# Telephone.net
KiCad netlist of a schematic drawn in Altium Designer
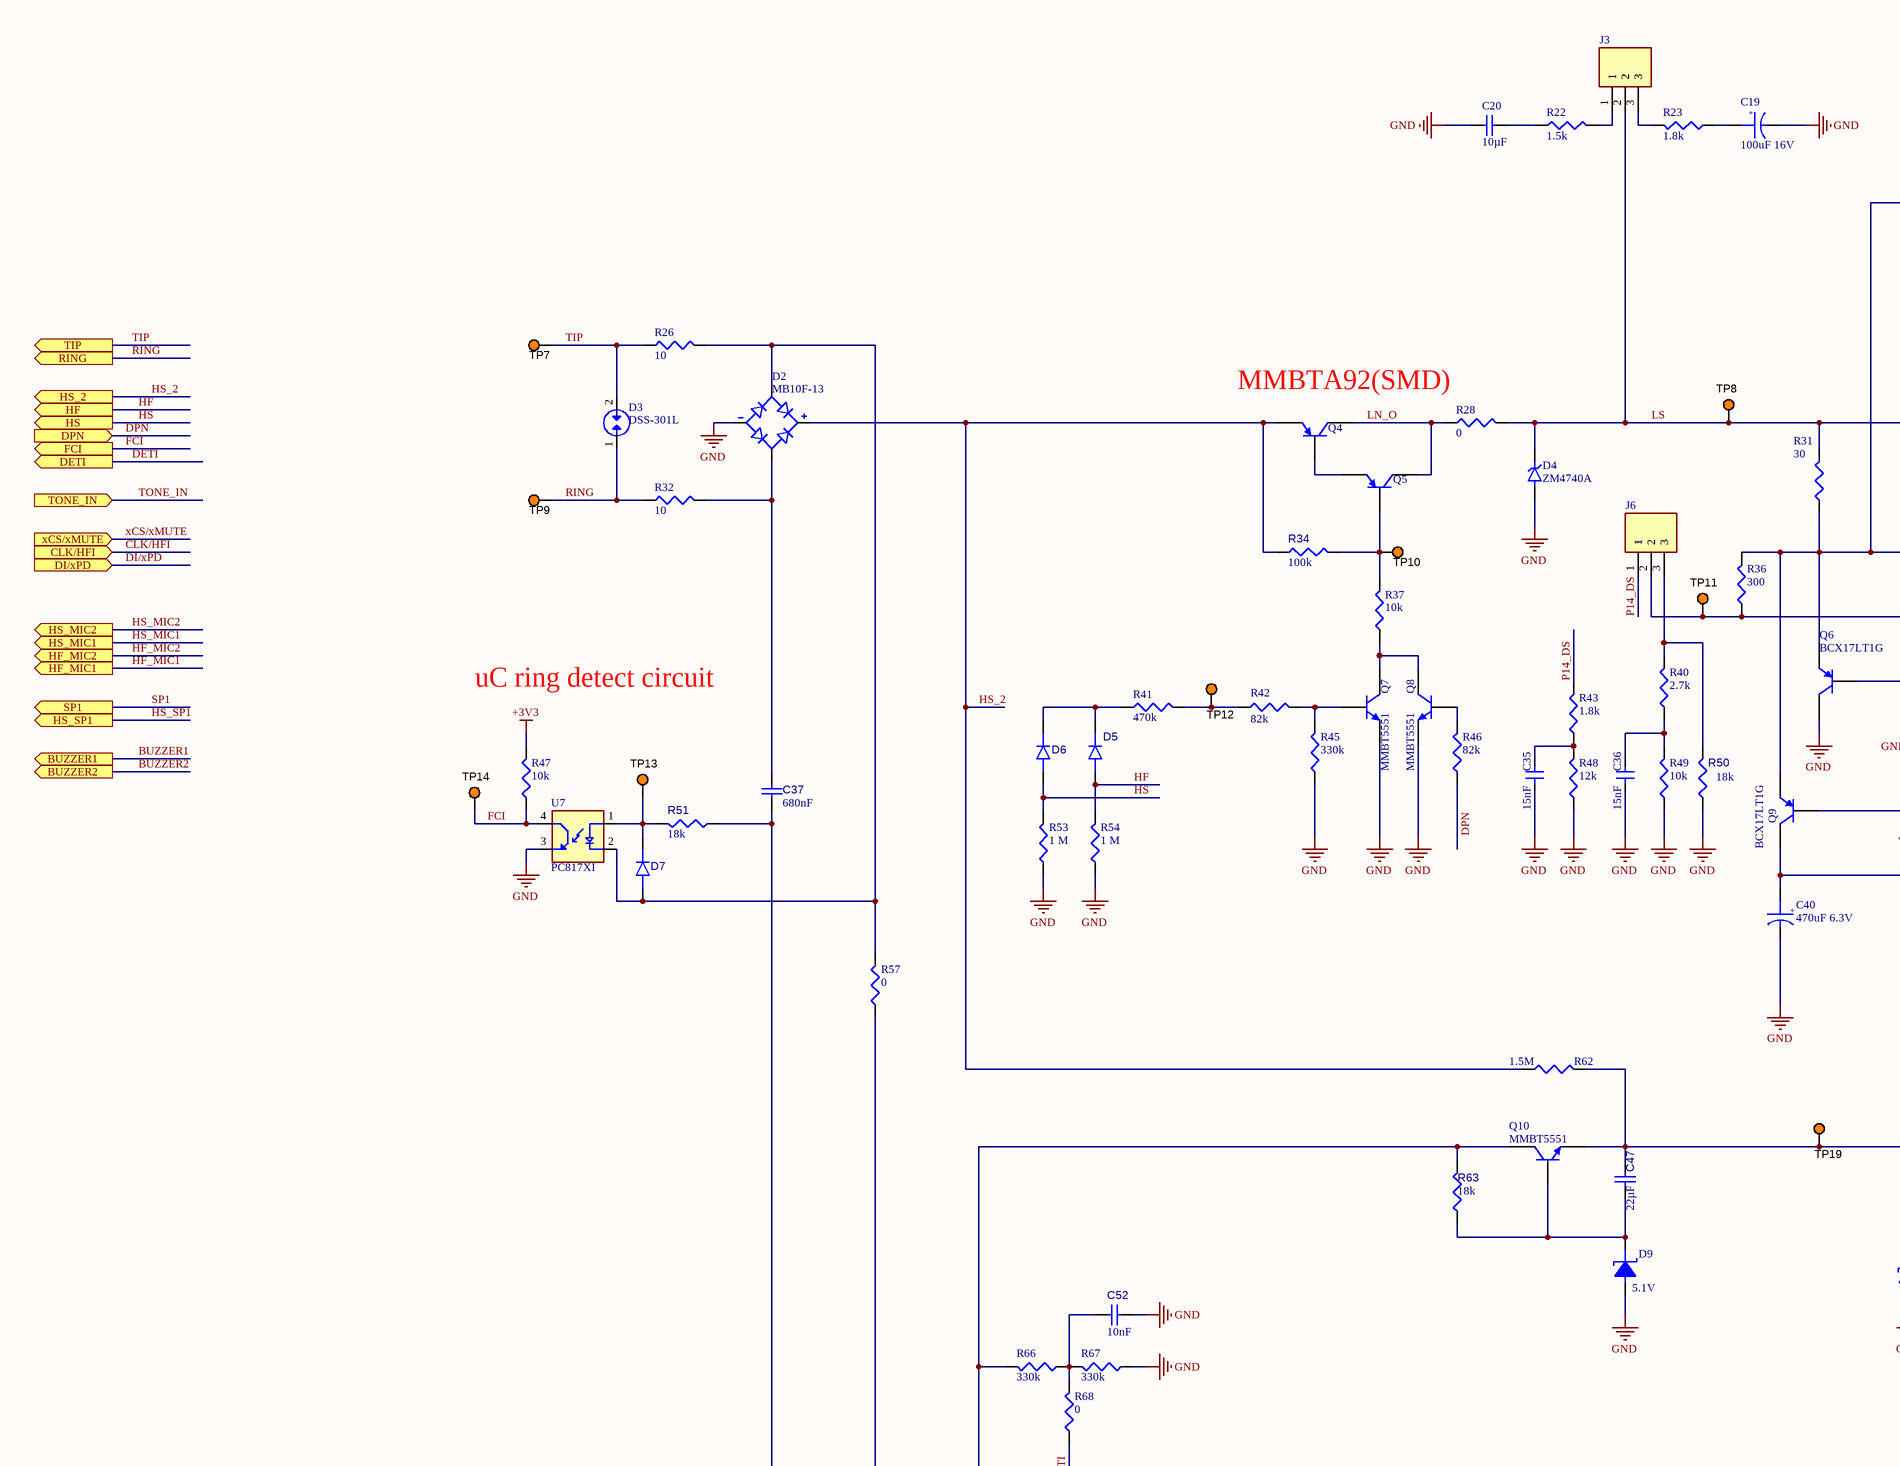
[diagram p0: Telephone.SchDoc, top left]
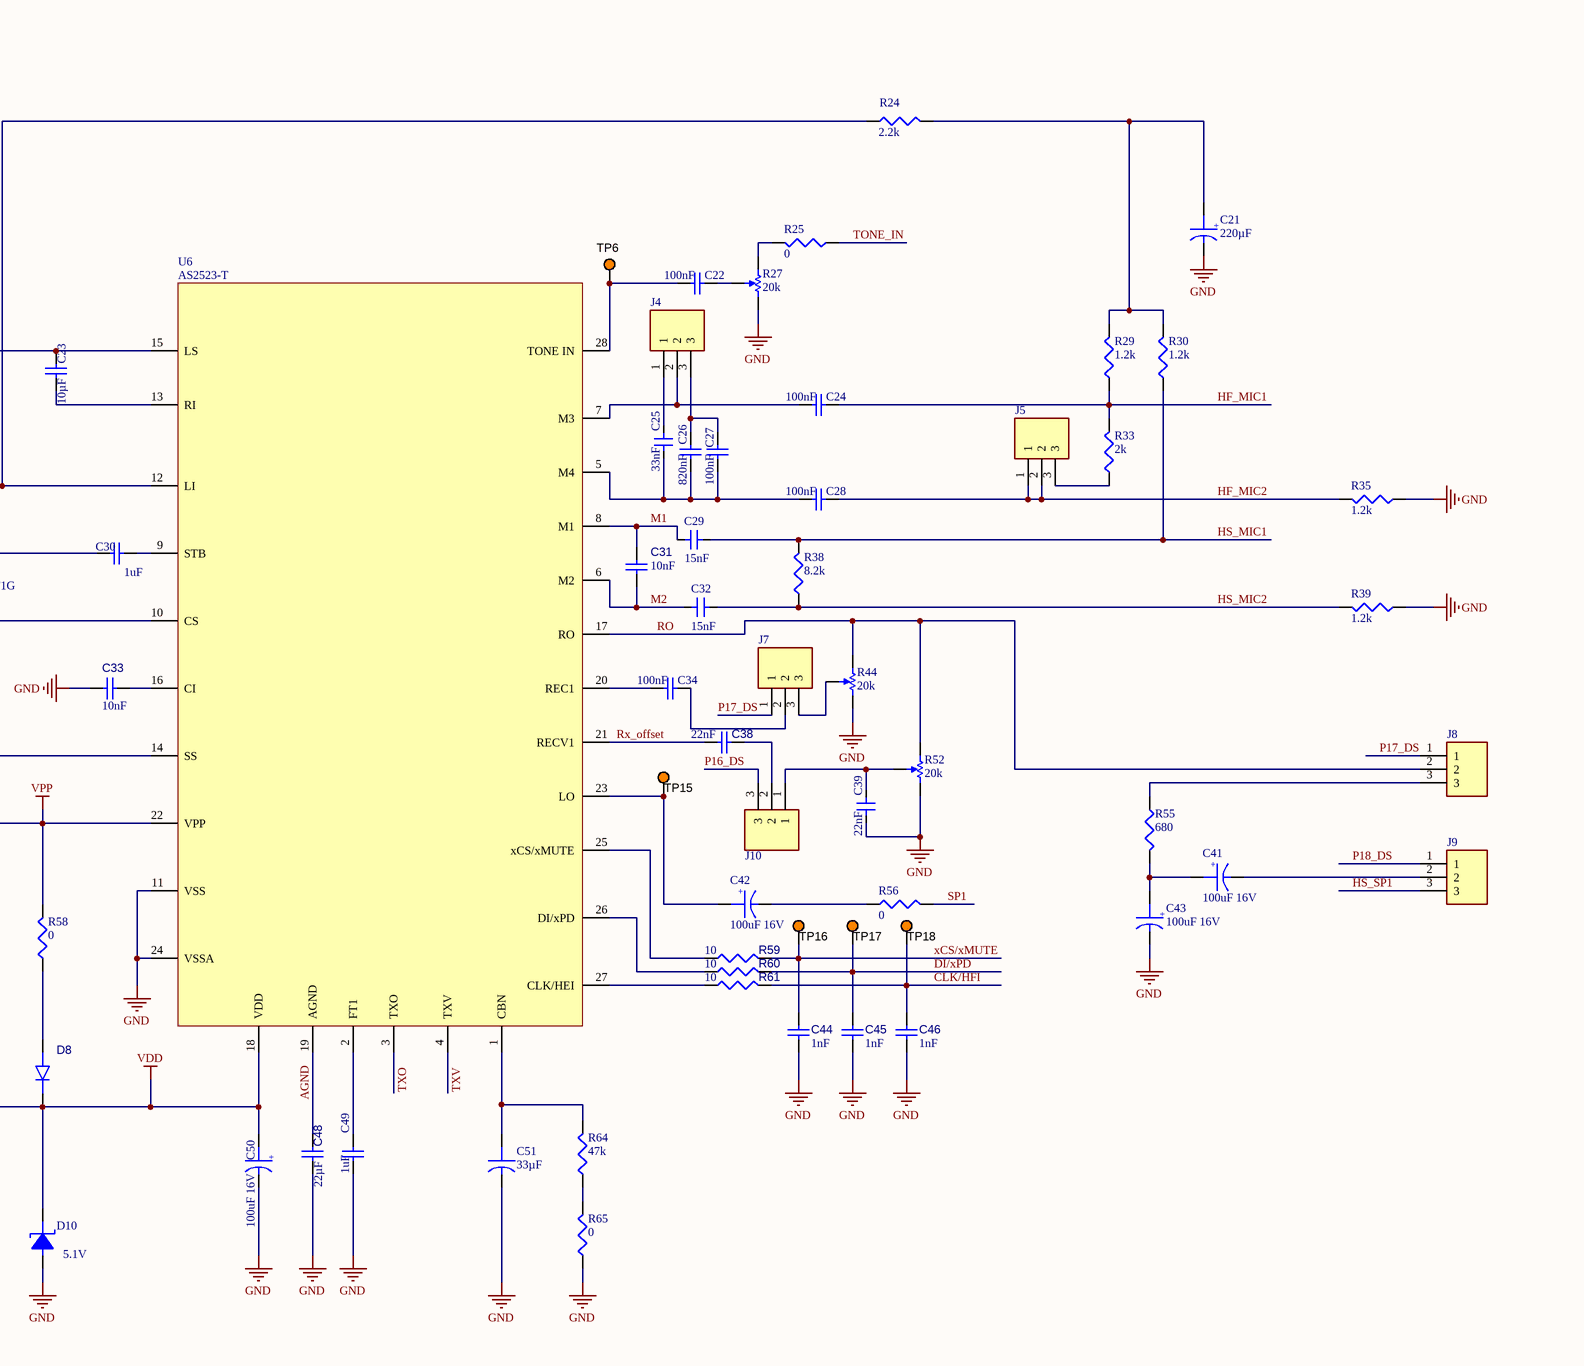
[diagram p1: Telephone.SchDoc, top right]
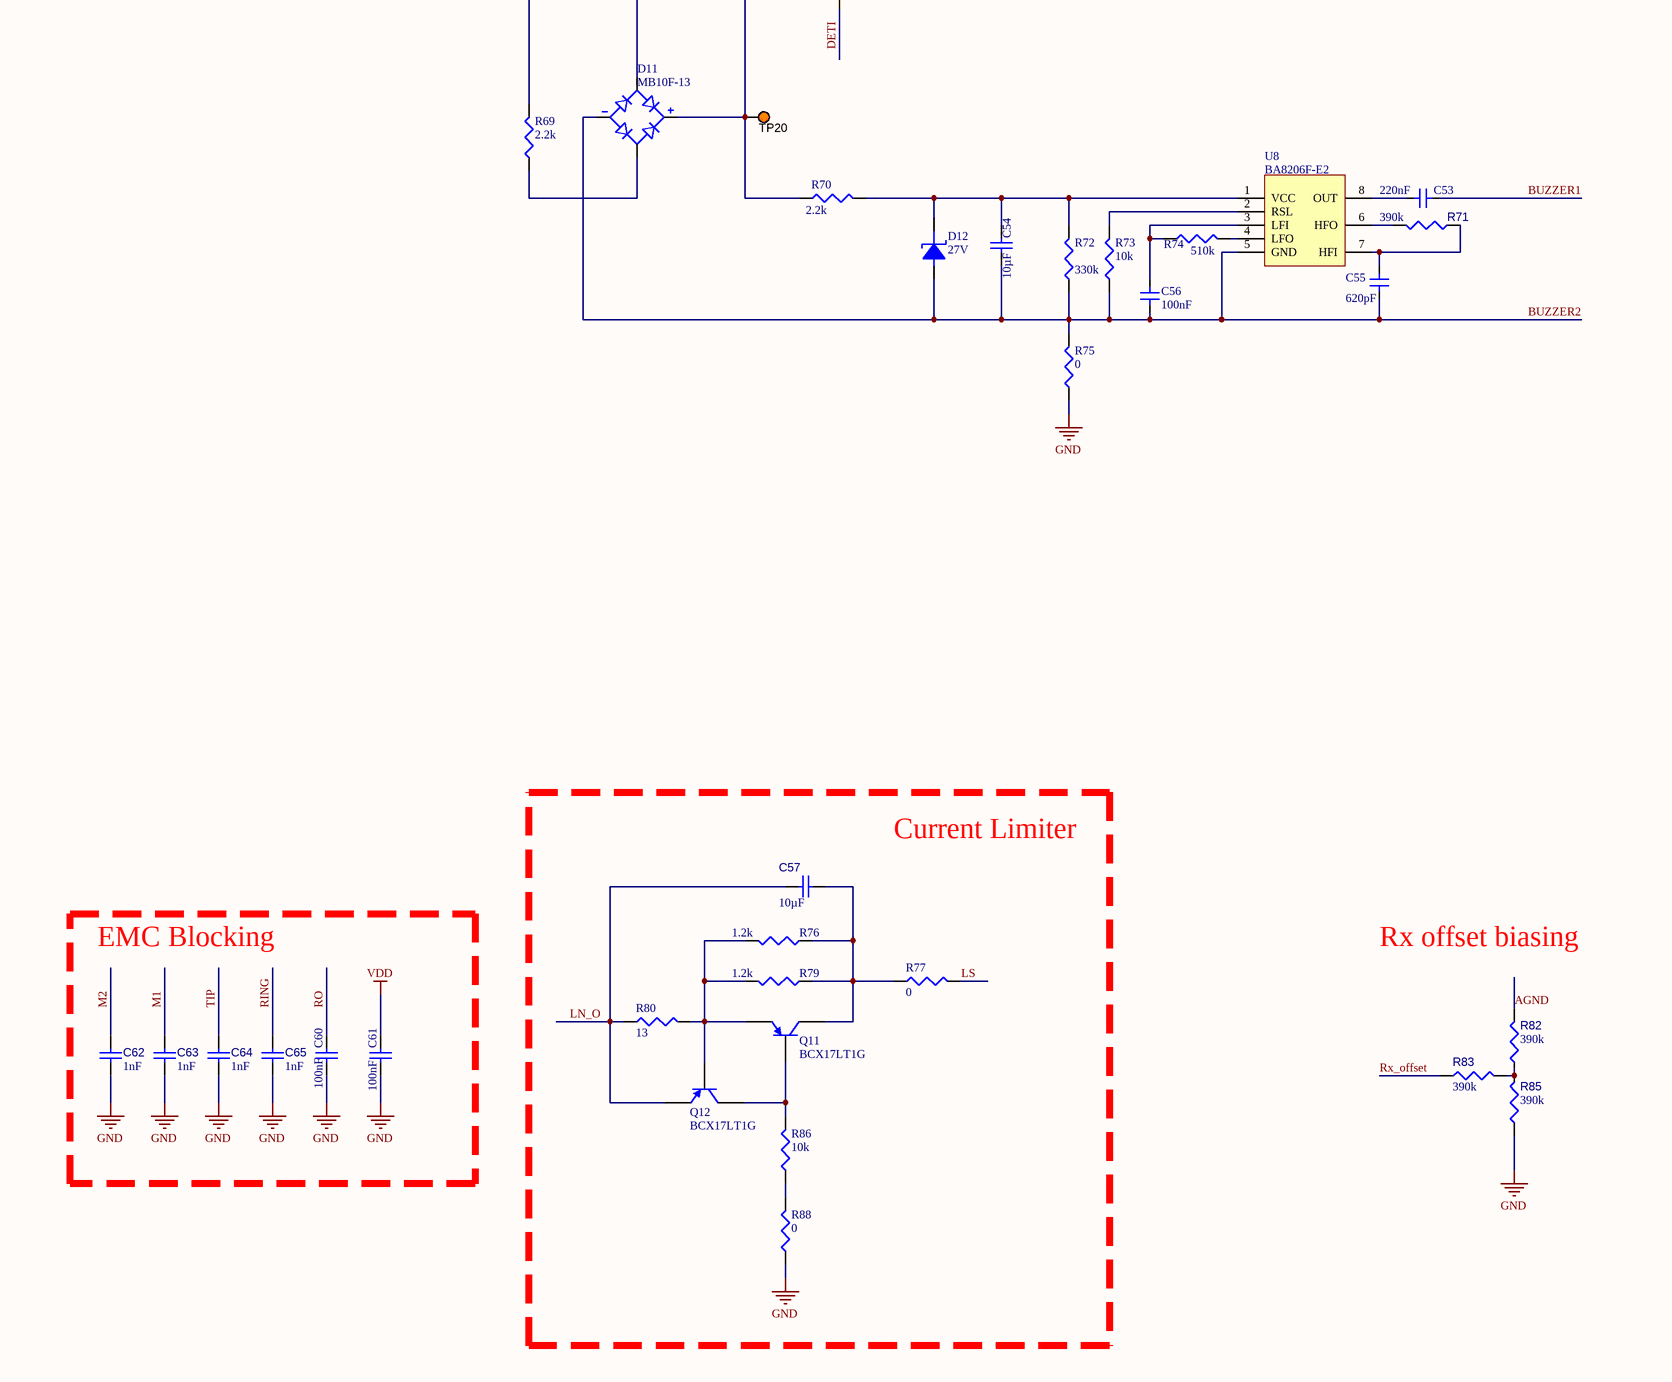
[diagram p2: Telephone.SchDoc, bottom left]
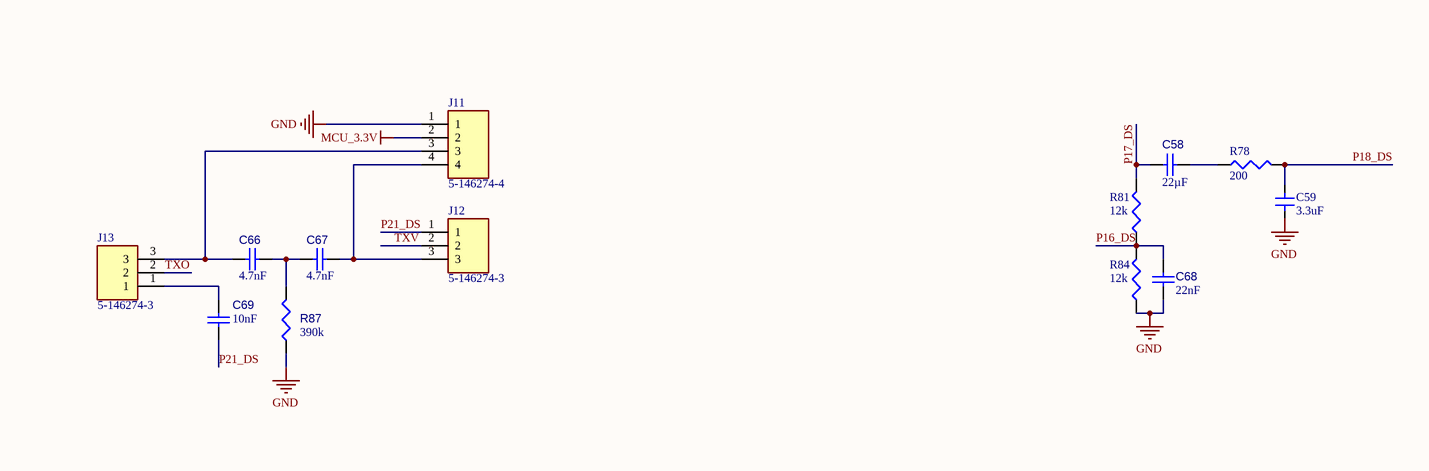
[diagram p3: Telephone.SchDoc, bottom right]

(export (version "E")
  (design (tool "Eeschema 10.0.6"))
  (components
    (comp (ref "C19")
      (value "100uF 16V")
      (footprint "CAPAE6767X56M 100UF 16V")
      (description "ALU Electrolytic; SMD; EEV; +105°C; 16VDC; 6.3µF; 6.3 x 5.4")
      (fields
        (field (name "MANUFACTURER") "KEMET")
        (field (name "MANUFACTURER PART NUMBER") "EEV107M016S9GAA")
      )
      (libsource (lib "Kish Spark") (part "EEV107M016S9GAA"))
    )
    (comp (ref "C20")
      (value "10µF")
      (footprint "C1210")
      (description "Capacitor 10 uF 35 VDC 1210, GRM32ER7YA106KA12L, Murata")
      (fields
        (field (name "TOLERANCE") "10%")
        (field (name "VOLTAGE") "35V")
        (field (name "SOURCE") "PTZLib.SchLib")
      )
      (libsource (lib "Kish Spark") (part "CAP-NP-2"))
    )
    (comp (ref "C21")
      (value "220µF")
      (footprint "CAPAE9290X56M 220UF 6.3V")
      (fields
        (field (name "MANUFACTURER") "Wurth Electronics")
        (field (name "MANUFACTURER PART NUMBER") "865080143009")
        (field (name "TOLERANCE") "20%")
      )
      (libsource (lib "Kish Spark") (part "EEV107M016S9GAA"))
    )
    (comp (ref "C22")
      (value "100nF")
      (footprint "C0603")
      (description "YAGEO - CC0603KRX7R8BB104 - CERAMIC CAPACITOR, 0.1UF, 25V, X7R, 10%, 0603, FULL REEL")
      (fields
        (field (name "TOLERANCE") "10%")
        (field (name "VOLTAGE") "25V")
        (field (name "SOURCE") "PTZLib.SchLib")
      )
      (libsource (lib "Kish Spark") (part "CAP-NP-2"))
    )
    (comp (ref "C23")
      (value "10µF")
      (footprint "C1210")
      (description "Capacitor 10 uF 35 VDC 1210, GRM32ER7YA106KA12L, Murata")
      (fields
        (field (name "TOLERANCE") "10%")
        (field (name "VOLTAGE") "35V")
        (field (name "SOURCE") "PTZLib.SchLib")
      )
      (libsource (lib "Kish Spark") (part "CAP-NP-2"))
    )
    (comp (ref "C24")
      (value "100nF")
      (footprint "C0603")
      (description "YAGEO - CC0603KRX7R8BB104 - CERAMIC CAPACITOR, 0.1UF, 25V, X7R, 10%, 0603, FULL REEL")
      (fields
        (field (name "TOLERANCE") "10%")
        (field (name "VOLTAGE") "25V")
        (field (name "SOURCE") "PTZLib.SchLib")
      )
      (libsource (lib "Kish Spark") (part "CAP-NP-2"))
    )
    (comp (ref "C25")
      (value "33nF")
      (footprint "0805")
      (description "Chip Capacitor 0805 MLCC X7R 0.033 uF+/ -20% 100 V T&R MH")
      (fields
        (field (name "MANUFACTURER") "Walsin Technologies")
        (field (name "MANUFACTURER PART NUMBER") "0805B333M101CT")
      )
      (libsource (lib "Kish Spark") (part "C0805C472K5RAC7210_1"))
    )
    (comp (ref "C26")
      (value "820nF")
      (footprint "C0603")
      (description "0603 820 nF 16 V ±10 % Tolerance X7R SMT Multilayer Ceramic Capacitor")
      (fields (field (name "TOLERANCE") "10%") (field (name "MANUFACTURER") "Yageo"))
      (libsource (lib "Kish Spark") (part "CAP-NP-2"))
    )
    (comp (ref "C27")
      (value "100nF")
      (footprint "C0603")
      (description "YAGEO - CC0603KRX7R8BB104 - CERAMIC CAPACITOR, 0.1UF, 25V, X7R, 10%, 0603, FULL REEL")
      (fields
        (field (name "TOLERANCE") "10%")
        (field (name "VOLTAGE") "25V")
        (field (name "SOURCE") "PTZLib.SchLib")
      )
      (libsource (lib "Kish Spark") (part "CAP-NP-2"))
    )
    (comp (ref "C28")
      (value "100nF")
      (footprint "C0603")
      (description "YAGEO - CC0603KRX7R8BB104 - CERAMIC CAPACITOR, 0.1UF, 25V, X7R, 10%, 0603, FULL REEL")
      (fields
        (field (name "TOLERANCE") "10%")
        (field (name "VOLTAGE") "25V")
        (field (name "SOURCE") "PTZLib.SchLib")
      )
      (libsource (lib "Kish Spark") (part "CAP-NP-2"))
    )
    (comp (ref "C29")
      (value "15nF")
      (footprint "0805")
      (description "Multilayer Ceramic Capacitor, 0.015 F, 10%, X7R, 50 V, 0805 [2012 Metric] RoHS Compliant: Yes")
      (fields
        (field (name "MANUFACTURER") "Walsin Technologies")
        (field (name "MANUFACTURER PART NUMBER") "0805B153K500CT")
      )
      (libsource (lib "Kish Spark") (part "C0805C472K5RAC7210_1"))
    )
    (comp (ref "C30")
      (value "1uF")
      (footprint "EVIDC:C0603")
      (description "Cap_1uF_10%_X5R_25V_0603")
      (fields (field (name "MANUFACTURER") "Samsung") (field (name "MFR PART NO") "CL10A105KA8NNNC"))
      (libsource (lib "EVIDC") (part "Cap_1uF_25V_0603"))
    )
    (comp (ref "C31")
      (value "10nF")
      (footprint "C0603")
      (description "0603 10nF 50 V ±10 % Tolerance X7R Surface Mount Multilayer Ceramic Capacitor")
      (fields (field (name "TOLERANCE") "10%") (field (name "MANUFACTURER") "Kyocera AVX"))
      (libsource (lib "Kish Spark") (part "CAP-NP-2"))
    )
    (comp (ref "C32")
      (value "15nF")
      (footprint "0805")
      (description "Multilayer Ceramic Capacitor, 0.015 F, 10%, X7R, 50 V, 0805 [2012 Metric] RoHS Compliant: Yes")
      (fields
        (field (name "MANUFACTURER") "Walsin Technologies")
        (field (name "MANUFACTURER PART NUMBER") "0805B153K500CT")
      )
      (libsource (lib "Kish Spark") (part "C0805C472K5RAC7210_1"))
    )
    (comp (ref "C33")
      (value "10nF")
      (footprint "C0603")
      (description "0603 10nF 50 V ±10 % Tolerance X7R Surface Mount Multilayer Ceramic Capacitor")
      (fields (field (name "TOLERANCE") "10%") (field (name "MANUFACTURER") "Kyocera AVX"))
      (libsource (lib "Kish Spark") (part "CAP-NP-2"))
    )
    (comp (ref "C34")
      (value "100nF")
      (footprint "C0603")
      (description "YAGEO - CC0603KRX7R8BB104 - CERAMIC CAPACITOR, 0.1UF, 25V, X7R, 10%, 0603, FULL REEL")
      (fields
        (field (name "TOLERANCE") "10%")
        (field (name "VOLTAGE") "25V")
        (field (name "SOURCE") "PTZLib.SchLib")
      )
      (libsource (lib "Kish Spark") (part "CAP-NP-2"))
    )
    (comp (ref "C35")
      (value "15nF")
      (footprint "0805")
      (description "Multilayer Ceramic Capacitor, 0.015 F, 10%, X7R, 50 V, 0805 [2012 Metric] RoHS Compliant: Yes")
      (fields
        (field (name "MANUFACTURER") "Walsin Technologies")
        (field (name "MANUFACTURER PART NUMBER") "0805B153K500CT")
      )
      (libsource (lib "Kish Spark") (part "C0805C472K5RAC7210_1"))
    )
    (comp (ref "C36")
      (value "15nF")
      (footprint "0805")
      (description "Multilayer Ceramic Capacitor, 0.015 F, 10%, X7R, 50 V, 0805 [2012 Metric] RoHS Compliant: Yes")
      (fields
        (field (name "MANUFACTURER") "Walsin Technologies")
        (field (name "MANUFACTURER PART NUMBER") "0805B153K500CT")
      )
      (libsource (lib "Kish Spark") (part "C0805C472K5RAC7210_1"))
    )
    (comp (ref "C37")
      (value "680nF")
      (footprint "C1812")
      (description "Cap Cer 0.68UF 250V X7R 1812")
      (fields
        (field (name "MANUFACTURER") "Walsin Technologies")
        (field (name "MANUFACTURER PART NUMBER") "1812B684M251CT")
      )
      (libsource (lib "Kish Spark") (part "CAP-NP-2"))
    )
    (comp (ref "C38")
      (value "22nF")
      (footprint "C0603")
      (description "Cap Ceramic 0.022uF 50V X7R 5% SMD 0603 150C Paper T/R")
      (fields (field (name "TOLERANCE") "5%") (field (name "Comment") "VJ0603Y223JXAAC"))
      (libsource (lib "Kish Spark") (part "CAP-NP-2"))
    )
    (comp (ref "C39")
      (value "22nF")
      (footprint "0805")
      (description "Surface Mount Ceramic Multilayer Capacitor 0.022uF 10% X7R 100V 0805 Paper T/R")
      (fields
        (field (name "MANUFACTURER") "Yageo")
        (field (name "MANUFACTURER PART NUMBER") "CC0805KRX7R0BB223")
      )
      (libsource (lib "Kish Spark") (part "C0805C472K5RAC7210_1"))
    )
    (comp (ref "C40")
      (value "470uF 6.3V")
      (footprint "CAPAE9984X105M 470UF 6.3V")
      (description "ALU Electrolytic; SMD; EDH; +105°C; 6.3VDC; 8µF; 8 x 10.2")
      (fields
        (field (name "MANUFACTURER") "KEMET")
        (field (name "MANUFACTURER PART NUMBER") "EDH477M6R3A9MAA")
      )
      (libsource (lib "Kish Spark") (part "EEV107M016S9GAA"))
    )
    (comp (ref "C41")
      (value "100uF 16V")
      (footprint "CAPAE6767X56M 100UF 16V")
      (description "ALU Electrolytic; SMD; EEV; +105°C; 16VDC; 6.3µF; 6.3 x 5.4")
      (fields
        (field (name "MANUFACTURER") "KEMET")
        (field (name "MANUFACTURER PART NUMBER") "EEV107M016S9GAA")
      )
      (libsource (lib "Kish Spark") (part "EEV107M016S9GAA"))
    )
    (comp (ref "C42")
      (value "100uF 16V")
      (footprint "CAPAE6767X56M 100UF 16V")
      (description "ALU Electrolytic; SMD; EEV; +105°C; 16VDC; 6.3µF; 6.3 x 5.4")
      (fields
        (field (name "MANUFACTURER") "KEMET")
        (field (name "MANUFACTURER PART NUMBER") "EEV107M016S9GAA")
      )
      (libsource (lib "Kish Spark") (part "EEV107M016S9GAA"))
    )
    (comp (ref "C43")
      (value "100uF 16V")
      (footprint "CAPAE6767X56M 100UF 16V")
      (description "ALU Electrolytic; SMD; EEV; +105°C; 16VDC; 6.3µF; 6.3 x 5.4")
      (fields
        (field (name "MANUFACTURER") "KEMET")
        (field (name "MANUFACTURER PART NUMBER") "EEV107M016S9GAA")
      )
      (libsource (lib "Kish Spark") (part "EEV107M016S9GAA"))
    )
    (comp (ref "C44")
      (value "1nF")
      (footprint "0603")
      (description "Cap, 1000PF, 250V, 10%, X7R, 0603")
      (fields (field (name "TOLERANCE") "10%") (field (name "MANUFACTURER") "Wurth Electronics"))
      (libsource (lib "Kish Spark") (part "CAP-NP-2"))
    )
    (comp (ref "C45")
      (value "1nF")
      (footprint "0603")
      (description "Cap, 1000PF, 250V, 10%, X7R, 0603")
      (fields (field (name "TOLERANCE") "10%") (field (name "MANUFACTURER") "Wurth Electronics"))
      (libsource (lib "Kish Spark") (part "CAP-NP-2"))
    )
    (comp (ref "C46")
      (value "1nF")
      (footprint "0603")
      (description "Cap, 1000PF, 250V, 10%, X7R, 0603")
      (fields (field (name "TOLERANCE") "10%") (field (name "MANUFACTURER") "Wurth Electronics"))
      (libsource (lib "Kish Spark") (part "CAP-NP-2"))
    )
    (comp (ref "C47")
      (value "22µF")
      (footprint "C0805")
      (description "Cap Ceramic 22uF 10V X5R 10% SMD 0805 85C T/R")
      (fields (field (name "TOLERANCE") "10%") (field (name "Comment") "CL21A226KPCLRNC"))
      (libsource (lib "Kish Spark") (part "CAP-NP-2"))
    )
    (comp (ref "C48")
      (value "22µF")
      (footprint "C0805")
      (description "Cap Ceramic 22uF 10V X5R 10% SMD 0805 85C T/R")
      (fields (field (name "TOLERANCE") "10%") (field (name "Comment") "CL21A226KPCLRNC"))
      (libsource (lib "Kish Spark") (part "CAP-NP-2"))
    )
    (comp (ref "C49")
      (value "1uF")
      (footprint "EVIDC:C0603")
      (description "Cap_1uF_10%_X5R_25V_0603")
      (fields (field (name "MANUFACTURER") "Samsung") (field (name "MFR PART NO") "CL10A105KA8NNNC"))
      (libsource (lib "EVIDC") (part "Cap_1uF_25V_0603"))
    )
    (comp (ref "C50")
      (value "100uF 16V")
      (footprint "CAPAE6767X56M 100UF 16V")
      (description "ALU Electrolytic; SMD; EEV; +105°C; 16VDC; 6.3µF; 6.3 x 5.4")
      (fields
        (field (name "MANUFACTURER") "KEMET")
        (field (name "MANUFACTURER PART NUMBER") "EEV107M016S9GAA")
      )
      (libsource (lib "Kish Spark") (part "EEV107M016S9GAA"))
    )
    (comp (ref "C51")
      (value "33µF")
      (footprint "CAPAE6342X55M 22UF 6.3V")
      (fields
        (field (name "MANUFACTURER") "Wurth Electronics")
        (field (name "MANUFACTURER PART NUMBER") "865080140003")
        (field (name "TOLERANCE") "20%")
      )
      (libsource (lib "Kish Spark") (part "865080140003"))
    )
    (comp (ref "C52")
      (value "10nF")
      (footprint "C0603")
      (description "0603 10nF 50 V ±10 % Tolerance X7R Surface Mount Multilayer Ceramic Capacitor")
      (fields (field (name "TOLERANCE") "10%") (field (name "MANUFACTURER") "Kyocera AVX"))
      (libsource (lib "Kish Spark") (part "CAP-NP-2"))
    )
    (comp (ref "C53")
      (value "220nF")
      (footprint "0805")
      (description "Cap Ceramic 0.22uF 50V X7R 10% SMD 0805 125°C Plastic T/R")
      (fields
        (field (name "MANUFACTURER") "KEMET")
        (field (name "MANUFACTURER PART NUMBER") "C0805C224K5RAC7210")
      )
      (libsource (lib "Kish Spark") (part "C0805C472K5RAC7210_1"))
    )
    (comp (ref "C54")
      (value "10µF")
      (footprint "C1210")
      (description "Capacitor 10 uF 35 VDC 1210, GRM32ER7YA106KA12L, Murata")
      (fields
        (field (name "TOLERANCE") "10%")
        (field (name "VOLTAGE") "35V")
        (field (name "SOURCE") "PTZLib.SchLib")
      )
      (libsource (lib "Kish Spark") (part "CAP-NP-2"))
    )
    (comp (ref "C55")
      (value "620pF")
      (footprint "0805")
      (fields
        (field (name "MANUFACTURER") "KEMET")
        (field (name "MANUFACTURER PART NUMBER") "C0805C621K1HACTU")
        (field (name "Comment") "CMP-001-00182-1")
      )
      (libsource (lib "Kish Spark") (part "C0805C472K5RAC7210_1"))
    )
    (comp (ref "C56")
      (value "100nF")
      (footprint "0805")
      (description "Capacitor, Ceramic; 0.1UF; Chip; Case 0805; +/-10%; 50WVDC; SMD; X7R; 2.5% Df; 0.037IN. ,")
      (fields
        (field (name "MANUFACTURER") "Kyocera AVX")
        (field (name "MANUFACTURER PART NUMBER") "08055C104KAT2A")
      )
      (libsource (lib "Kish Spark") (part "C0805C472K5RAC7210_1"))
    )
    (comp (ref "C57")
      (value "10µF")
      (footprint "C1210")
      (description "3225 C 10uF Ceramic Multilayer Capacitor; 50 V; +85degC; X7R Dielectric; +/-20%")
      (fields (field (name "TOLERANCE") "20%") (field (name "MANUFACTURER") "KEMET"))
      (libsource (lib "Kish Spark") (part "CAP-NP-2"))
    )
    (comp (ref "C58")
      (value "22µF")
      (footprint "C0805")
      (description "Cap Ceramic 22uF 10V X5R 10% SMD 0805 85C T/R")
      (fields (field (name "TOLERANCE") "10%") (field (name "Comment") "CL21A226KPCLRNC"))
      (libsource (lib "Kish Spark") (part "CAP-NP-2"))
    )
    (comp (ref "C59")
      (value "3.3uF")
      (footprint "0603")
      (description "Chip Capacitor 0603 MLCC X5R 3.3 uF+/- 10% 6.3 V T&R GP")
      (fields
        (field (name "MANUFACTURER") "Walsin Technologies")
        (field (name "MANUFACTURER PART NUMBER") "0603X335K6R3CT")
      )
      (libsource (lib "Kish Spark") (part "C0805C472K5RAC7210_1"))
    )
    (comp (ref "C60")
      (value "100nF")
      (footprint "C0603")
      (description "YAGEO - CC0603KRX7R8BB104 - CERAMIC CAPACITOR, 0.1UF, 25V, X7R, 10%, 0603, FULL REEL")
      (fields
        (field (name "TOLERANCE") "10%")
        (field (name "VOLTAGE") "25V")
        (field (name "SOURCE") "PTZLib.SchLib")
      )
      (libsource (lib "Kish Spark") (part "CAP-NP-2"))
    )
    (comp (ref "C61")
      (value "100nF")
      (footprint "C0603")
      (description "YAGEO - CC0603KRX7R8BB104 - CERAMIC CAPACITOR, 0.1UF, 25V, X7R, 10%, 0603, FULL REEL")
      (fields
        (field (name "TOLERANCE") "10%")
        (field (name "VOLTAGE") "25V")
        (field (name "SOURCE") "PTZLib.SchLib")
      )
      (libsource (lib "Kish Spark") (part "CAP-NP-2"))
    )
    (comp (ref "C62")
      (value "1nF")
      (footprint "0603")
      (description "Cap, 1000PF, 250V, 10%, X7R, 0603")
      (fields (field (name "TOLERANCE") "10%") (field (name "MANUFACTURER") "Wurth Electronics"))
      (libsource (lib "Kish Spark") (part "CAP-NP-2"))
    )
    (comp (ref "C63")
      (value "1nF")
      (footprint "0603")
      (description "Cap, 1000PF, 250V, 10%, X7R, 0603")
      (fields (field (name "TOLERANCE") "10%") (field (name "MANUFACTURER") "Wurth Electronics"))
      (libsource (lib "Kish Spark") (part "CAP-NP-2"))
    )
    (comp (ref "C64")
      (value "1nF")
      (footprint "0603")
      (description "Cap, 1000PF, 250V, 10%, X7R, 0603")
      (fields (field (name "TOLERANCE") "10%") (field (name "MANUFACTURER") "Wurth Electronics"))
      (libsource (lib "Kish Spark") (part "CAP-NP-2"))
    )
    (comp (ref "C65")
      (value "1nF")
      (footprint "0603")
      (description "Cap, 1000PF, 250V, 10%, X7R, 0603")
      (fields (field (name "TOLERANCE") "10%") (field (name "MANUFACTURER") "Wurth Electronics"))
      (libsource (lib "Kish Spark") (part "CAP-NP-2"))
    )
    (comp (ref "C66")
      (value "4.7nF")
      (footprint "C0805")
      (description "Cap Ceramic 0.0047uF 50V X7R 10% SMD 0805 125°C Paper T/R")
      (fields (field (name "TOLERANCE") "10%") (field (name "Comment") "CMP-001-00190-1"))
      (libsource (lib "Kish Spark") (part "CAP-NP-2"))
    )
    (comp (ref "C67")
      (value "4.7nF")
      (footprint "C0805")
      (description "Cap Ceramic 0.0047uF 50V X7R 10% SMD 0805 125°C Paper T/R")
      (fields (field (name "TOLERANCE") "10%") (field (name "Comment") "CMP-001-00190-1"))
      (libsource (lib "Kish Spark") (part "CAP-NP-2"))
    )
    (comp (ref "C68")
      (value "22nF")
      (footprint "C0603")
      (description "Cap Ceramic 0.022uF 50V X7R 5% SMD 0603 150C Paper T/R")
      (fields (field (name "TOLERANCE") "5%") (field (name "Comment") "VJ0603Y223JXAAC"))
      (libsource (lib "Kish Spark") (part "CAP-NP-2"))
    )
    (comp (ref "C69")
      (value "10nF")
      (footprint "C0603")
      (description "0603 10nF 50 V ±10 % Tolerance X7R Surface Mount Multilayer Ceramic Capacitor")
      (fields (field (name "TOLERANCE") "10%") (field (name "MANUFACTURER") "Kyocera AVX"))
      (libsource (lib "Kish Spark") (part "CAP-NP-2"))
    )
    (comp (ref "D2")
      (value "MB10F-13")
      (footprint "DIOB_MB10F-13")
      (description "Bridge Rectifier Single Phase Standard 1 kV Surface Mount MBF")
      (fields (field (name "MANUFACTURER") "Diodes"))
      (libsource (lib "Kish Spark") (part "bridge-rectifier"))
    )
    (comp (ref "D3")
      (value "DSS-301L")
      (footprint "DSS")
      (description "MITSUBISHI MATERIALS DSS Series 300V 0.5kA Through Hole Surge Absorber Gas Discharge Tube (GDT)")
      (fields (field (name "MANUFACTURER") "Mitsubishi"))
      (libsource (lib "Kish Spark") (part "2031-23T-SM-RPLF"))
    )
    (comp (ref "D4")
      (value "ZM4740A")
      (footprint "DIOMELF5124N")
      (description "Zener Diodes 10 Volt 1 Watt 5%")
      (fields (field (name "MANUFACTURER PART NUMBER") "ZM4740A_L0G"))
      (libsource (lib "Kish Spark") (part "ZM4740A_L0G"))
    )
    (comp (ref "D5")
      (value "MURS140-E3/5BT")
      (footprint "DO-214AA-2")
      (description "MURS140 Series 400 V 1 A 75 ns SMT Ultrafast Plastic Rectifier - DO-214AA")
      (libsource (lib "Kish Spark") (part "DIODE-2"))
    )
    (comp (ref "D6")
      (value "MURS140-E3/5BT")
      (footprint "DO-214AA-2")
      (description "MURS140 Series 400 V 1 A 75 ns SMT Ultrafast Plastic Rectifier - DO-214AA")
      (libsource (lib "Kish Spark") (part "DIODE-2"))
    )
    (comp (ref "D7")
      (value "1N4148W_R1_00001")
      (footprint "SOD-123")
      (description "Si-diode 0, 15A 100V SOD123")
      (fields (field (name "MANUFACTURER") "Pan Jit"))
      (libsource (lib "Kish Spark") (part "DIODE-2"))
    )
    (comp (ref "D8")
      (value "1N4148W_R1_00001")
      (footprint "SOD-123")
      (description "Si-diode 0, 15A 100V SOD123")
      (fields (field (name "MANUFACTURER") "Pan Jit"))
      (libsource (lib "Kish Spark") (part "DIODE-2"))
    )
    (comp (ref "D9")
      (value "5.1V")
      (footprint "Zener 5.1V")
      (description "Diode Zener Single 5.1V 2.564% 200mW Automotive 2-Pin SOD-323 T/R")
      (fields (field (name "MANUFACTURER") "Diodes") (field (name "MANUFACTURER PART NUMBER") "DDZ5V1BS-7"))
      (libsource (lib "Kish Spark") (part "MM3Z27VST1G"))
    )
    (comp (ref "D10")
      (value "5.1V")
      (footprint "Zener 5.1V")
      (description "Diode Zener Single 5.1V 2.564% 200mW Automotive 2-Pin SOD-323 T/R")
      (fields (field (name "MANUFACTURER") "Diodes") (field (name "MANUFACTURER PART NUMBER") "DDZ5V1BS-7"))
      (libsource (lib "Kish Spark") (part "MM3Z27VST1G"))
    )
    (comp (ref "D11")
      (value "MB10F-13")
      (footprint "DIOB_MB10F-13")
      (description "Bridge Rectifier Single Phase Standard 1 kV Surface Mount MBF")
      (fields (field (name "MANUFACTURER") "Diodes"))
      (libsource (lib "Kish Spark") (part "bridge-rectifier"))
    )
    (comp (ref "D12")
      (value "27V")
      (footprint "Diode - 27V")
      (description "On a Reel of 3000, ON Semiconductor, 27V Zener Diode 2% 300 mW SMT 2-Pin SOD-323, RL")
      (fields
        (field (name "MANUFACTURER") "ON Semiconductor")
        (field (name "MANUFACTURER PART NUMBER") "MM3Z27VST1G")
      )
      (libsource (lib "Kish Spark") (part "MM3Z27VST1G"))
    )
    (comp (ref "J3")
      (value "5-146274-3")
      (footprint "TE_5-146274-3")
      (description "Conn Unshrouded Header HDR 3 POS 2.54mm Solder ST Top Entry Thru-Hole Carton")
      (fields (field (name "MANUFACTURER") "TE Connectivity"))
      (libsource (lib "") (part "5-146274-3_1"))
    )
    (comp (ref "J4")
      (value "5-146274-3")
      (footprint "TE_5-146274-3")
      (description "Conn Unshrouded Header HDR 3 POS 2.54mm Solder ST Top Entry Thru-Hole Carton")
      (fields (field (name "MANUFACTURER") "TE Connectivity"))
      (libsource (lib "") (part "5-146274-3_1"))
    )
    (comp (ref "J5")
      (value "5-146274-3")
      (footprint "TE_5-146274-3")
      (description "Conn Unshrouded Header HDR 3 POS 2.54mm Solder ST Top Entry Thru-Hole Carton")
      (fields (field (name "MANUFACTURER") "TE Connectivity"))
      (libsource (lib "") (part "5-146274-3_1"))
    )
    (comp (ref "J6")
      (value "5-146274-3")
      (footprint "TE_5-146274-3")
      (description "Conn Unshrouded Header HDR 3 POS 2.54mm Solder ST Top Entry Thru-Hole Carton")
      (fields (field (name "MANUFACTURER") "TE Connectivity"))
      (libsource (lib "") (part "5-146274-3_1"))
    )
    (comp (ref "J7")
      (value "5-146274-3")
      (footprint "TE_5-146274-3")
      (description "Conn Unshrouded Header HDR 3 POS 2.54mm Solder ST Top Entry Thru-Hole Carton")
      (fields (field (name "MANUFACTURER") "TE Connectivity"))
      (libsource (lib "") (part "5-146274-3_1"))
    )
    (comp (ref "J8")
      (value "5-146274-3")
      (footprint "TE_5-146274-3")
      (description "Conn Unshrouded Header HDR 3 POS 2.54mm Solder ST Top Entry Thru-Hole Carton")
      (fields (field (name "MANUFACTURER") "TE Connectivity"))
      (libsource (lib "") (part "5-146274-3_2"))
    )
    (comp (ref "J9")
      (value "5-146274-3")
      (footprint "TE_5-146274-3")
      (description "Conn Unshrouded Header HDR 3 POS 2.54mm Solder ST Top Entry Thru-Hole Carton")
      (fields (field (name "MANUFACTURER") "TE Connectivity"))
      (libsource (lib "") (part "5-146274-3_2"))
    )
    (comp (ref "J10")
      (value "5-146274-3")
      (footprint "TE_5-146274-3")
      (description "Conn Unshrouded Header HDR 3 POS 2.54mm Solder ST Top Entry Thru-Hole Carton")
      (fields (field (name "MANUFACTURER") "TE Connectivity"))
      (libsource (lib "") (part "5-146274-3_4"))
    )
    (comp (ref "J11")
      (value "5-146274-4")
      (footprint "5-146274-3")
      (description "5-146274-4 ; ROHS ; TYCO ; AMPMODU Breakaway Heade rs 4P HEADER TIN single r ow")
      (libsource (lib "") (part "5-146274-3_3"))
    )
    (comp (ref "J12")
      (value "5-146274-3")
      (footprint "TE_5-146274-3")
      (description "Conn Unshrouded Header HDR 3 POS 2.54mm Solder ST Top Entry Thru-Hole Carton")
      (fields (field (name "MANUFACTURER") "TE Connectivity"))
      (libsource (lib "") (part "5-146274-3_2"))
    )
    (comp (ref "J13")
      (value "5-146274-3")
      (footprint "TE_5-146274-3")
      (description "Conn Unshrouded Header HDR 3 POS 2.54mm Solder ST Top Entry Thru-Hole Carton")
      (fields (field (name "MANUFACTURER") "TE Connectivity"))
      (libsource (lib "Kish Spark") (part "5-146274-3"))
    )
    (comp (ref "Q4")
      (value "MPSA92PBFREE")
      (footprint "UNIC-TO-92-3")
      (description "MPSA92 Series 300 V 500 mA PNP Through Hole Silicon Transistor - TO-92")
      (fields (field (name "MANUFACTURER") "Central Semiconductor"))
      (libsource (lib "Kish Spark") (part "BJT-PNP-EBC-3"))
    )
    (comp (ref "Q5")
      (value "MPSA92PBFREE")
      (footprint "UNIC-TO-92-3")
      (description "MPSA92 Series 300 V 500 mA PNP Through Hole Silicon Transistor - TO-92")
      (fields (field (name "MANUFACTURER") "Central Semiconductor"))
      (libsource (lib "Kish Spark") (part "BJT-PNP-EBC-3"))
    )
    (comp (ref "Q6")
      (value "BCX17LT1G")
      (footprint "FAIR-SOT23-3_V")
      (description "ON Semi BCX17LT1G PNP Bipolar Transistor; 0.5 A; 45 V; 3-Pin SOT-23")
      (fields (field (name "MANUFACTURER") "ON Semiconductor"))
      (libsource (lib "Kish Spark") (part "BJT-PNP-BEC-3"))
    )
    (comp (ref "Q7")
      (value "MMBT5551")
      (footprint "SOT23127P600-8N")
      (description "Bipolar Transistor, SOT-23, 160V, 600mA")
      (fields
        (field (name "MANUFACTURER") "ON Semiconductor")
        (field (name "MANUFACTURER PART NUMBER") "MMBT5551LT1G")
      )
      (libsource (lib "Kish Spark") (part "BJT-NPN-EBC-3"))
    )
    (comp (ref "Q8")
      (value "MMBT5551")
      (footprint "SOT23127P600-8N")
      (description "Bipolar Transistor, SOT-23, 160V, 600mA")
      (fields
        (field (name "MANUFACTURER") "ON Semiconductor")
        (field (name "MANUFACTURER PART NUMBER") "MMBT5551LT1G")
      )
      (libsource (lib "Kish Spark") (part "BJT-NPN-EBC-3"))
    )
    (comp (ref "Q9")
      (value "BCX17LT1G")
      (footprint "FAIR-SOT23-3_V")
      (description "ON Semi BCX17LT1G PNP Bipolar Transistor; 0.5 A; 45 V; 3-Pin SOT-23")
      (fields (field (name "MANUFACTURER") "ON Semiconductor"))
      (libsource (lib "Kish Spark") (part "BJT-PNP-BEC-3"))
    )
    (comp (ref "Q10")
      (value "MMBT5551")
      (footprint "SOT23127P600-8N")
      (description "Bipolar Transistor, SOT-23, 160V, 600mA")
      (fields
        (field (name "MANUFACTURER") "ON Semiconductor")
        (field (name "MANUFACTURER PART NUMBER") "MMBT5551LT1G")
      )
      (libsource (lib "Kish Spark") (part "BJT-NPN-EBC-3"))
    )
    (comp (ref "Q11")
      (value "BCX17LT1G")
      (footprint "FAIR-SOT23-3_V")
      (description "ON Semi BCX17LT1G PNP Bipolar Transistor; 0.5 A; 45 V; 3-Pin SOT-23")
      (fields (field (name "MANUFACTURER") "ON Semiconductor"))
      (libsource (lib "Kish Spark") (part "BJT-PNP-BEC-3"))
    )
    (comp (ref "Q12")
      (value "BCX17LT1G")
      (footprint "FAIR-SOT23-3_V")
      (description "ON Semi BCX17LT1G PNP Bipolar Transistor; 0.5 A; 45 V; 3-Pin SOT-23")
      (fields (field (name "MANUFACTURER") "ON Semiconductor"))
      (libsource (lib "Kish Spark") (part "BJT-PNP-BEC-3"))
    )
    (comp (ref "R22")
      (value "1.5k")
      (footprint "0805")
      (description "Res Thick Film 0805 1.5K Ohm 5% 1/8W ±200ppm/°C Molded SMD SMD Paper T/R")
      (fields
        (field (name "MANUFACTURER") "Vishay Dale")
        (field (name "MANUFACTURER PART NUMBER") "CRCW08051K50JNEA")
      )
      (libsource (lib "Kish Spark") (part "RC0805FR-1018KL (2)"))
    )
    (comp (ref "R23")
      (value "1.8k")
      (footprint "0805")
      (description "Res Thick Film 0805 1.8K Ohm 5% 1/8W ±200ppm/°C Molded SMD SMD Paper T/R")
      (fields
        (field (name "MANUFACTURER") "Vishay Dale")
        (field (name "MANUFACTURER PART NUMBER") "CRCW08051K80JNEA")
      )
      (libsource (lib "Kish Spark") (part "RC0805FR-1018KL (2)"))
    )
    (comp (ref "R24")
      (value "2.2k")
      (footprint "0805")
      (description "Res Thick Film 0805 2.2K Ohm 5% 1/8W ±200ppm/°C Molded SMD SMD Paper Tape on Plastic Reel")
      (fields
        (field (name "MANUFACTURER") "Bourns")
        (field (name "MANUFACTURER PART NUMBER") "CR0805-JW-222ELF")
      )
      (libsource (lib "Kish Spark") (part "RC0805FR-1018KL (2)"))
    )
    (comp (ref "R25")
      (value "0")
      (footprint "R0603")
      (description "Res Thkflm 0603 0 Ohm Jumper 1/10W 100Ppm/ C Smd Rohs Compliant: Yes")
      (fields (field (name "Comment") "RMCF0603ZT0R00") (field (name "SOURCE") "PTZLib.SchLib"))
      (libsource (lib "Kish Spark") (part "CRCW060349R9FKEAC"))
    )
    (comp (ref "R26")
      (value "10")
      (footprint "R2512")
      (description "Res Thick Film 2512 10 Ohm 5% 3W ±200ppm/C Pad SMD T/R")
      (fields
        (field (name "MANUFACTURER") "TE Connectivity CGS")
        (field (name "MANUFACTURER PART NUMBER") "1-2176230-4")
      )
      (libsource (lib "Kish Spark") (part "RC0805FR-1018KL (2)"))
    )
    (comp (ref "R27")
      (value "20k")
      (footprint "BOUR-TC33X-2_V")
      (description "Res Trimmer 20K Ohm 25% 1/10W 1(Elec)/1(Mech)Turn (3 X 3.8mm) Foot Print SMD Embossed T/R")
      (fields (field (name "POWER") "100mW") (field (name "TOLERANCE") "25%"))
      (libsource (lib "Kish Spark") (part "RES-ADJ-3_A"))
    )
    (comp (ref "R28")
      (value "0")
      (footprint "R0603")
      (description "Res Thkflm 0603 0 Ohm Jumper 1/10W 100Ppm/ C Smd Rohs Compliant: Yes")
      (fields (field (name "Comment") "RMCF0603ZT0R00") (field (name "SOURCE") "PTZLib.SchLib"))
      (libsource (lib "Kish Spark") (part "CRCW060349R9FKEAC"))
    )
    (comp (ref "R29")
      (value "1.2k")
      (footprint "0805")
      (description "Res Thick Film 0805 1.2K Ohm 1% 0.125W(1/8W) ±100ppm/C Molded SMD Paper Tape on Plastic Reel")
      (fields
        (field (name "MANUFACTURER") "Bourns")
        (field (name "MANUFACTURER PART NUMBER") "CR0805-FX-1201ELF")
      )
      (libsource (lib "Kish Spark") (part "RC0805FR-1018KL (2)"))
    )
    (comp (ref "R30")
      (value "1.2k")
      (footprint "0805")
      (description "Res Thick Film 0805 1.2K Ohm 1% 0.125W(1/8W) ±100ppm/C Molded SMD Paper Tape on Plastic Reel")
      (fields
        (field (name "MANUFACTURER") "Bourns")
        (field (name "MANUFACTURER PART NUMBER") "CR0805-FX-1201ELF")
      )
      (libsource (lib "Kish Spark") (part "RC0805FR-1018KL (2)"))
    )
    (comp (ref "R31")
      (value "30")
      (footprint "0603")
      (description "Res Thick Film 0603 30 Ohm 1% 0.2W(1/5W) ±200ppm/°C Molded SMD Punched Carrier T/R")
      (fields
        (field (name "MANUFACTURER") "Panasonic")
        (field (name "MANUFACTURER PART NUMBER") "ERJP03F30R0V")
      )
      (libsource (lib "Kish Spark") (part "RC0805FR-1018KL (2)"))
    )
    (comp (ref "R32")
      (value "10")
      (footprint "R2512")
      (description "Res Thick Film 2512 10 Ohm 5% 3W ±200ppm/C Pad SMD T/R")
      (fields
        (field (name "MANUFACTURER") "TE Connectivity CGS")
        (field (name "MANUFACTURER PART NUMBER") "1-2176230-4")
      )
      (libsource (lib "Kish Spark") (part "RC0805FR-1018KL (2)"))
    )
    (comp (ref "R33")
      (value "2k")
      (footprint "0805")
      (description "Res Thick Film 0805 2K Ohm 5% 1/8W ±200ppm/°C Molded SMD SMD Paper Tape on Plastic Reel")
      (fields
        (field (name "MANUFACTURER") "Bourns")
        (field (name "MANUFACTURER PART NUMBER") "CR0805-JW-202ELF")
      )
      (libsource (lib "Kish Spark") (part "RC0805FR-1018KL (2)"))
    )
    (comp (ref "R34")
      (value "100k")
      (footprint "R0805")
      (description "Res Thick Film 0805 100K Ohm 1% 1/8W ±100ppm/°C Molded SMD Paper T/R")
      (fields (field (name "POWER") "125mW") (field (name "TOLERANCE") "1%"))
      (libsource (lib "Kish Spark") (part "RES-2"))
    )
    (comp (ref "R35")
      (value "1.2k")
      (footprint "0805")
      (description "Res Thick Film 0805 1.2K Ohm 1% 0.125W(1/8W) ±100ppm/C Molded SMD Paper Tape on Plastic Reel")
      (fields
        (field (name "MANUFACTURER") "Bourns")
        (field (name "MANUFACTURER PART NUMBER") "CR0805-FX-1201ELF")
      )
      (libsource (lib "Kish Spark") (part "RC0805FR-1018KL (2)"))
    )
    (comp (ref "R36")
      (value "300")
      (footprint "0805")
      (description "Res Thick Film 0805 300 Ohm 1% 1/8W ±100ppm/°C Molded SMD SMD Paper Tape on Plastic Reel")
      (fields
        (field (name "MANUFACTURER") "Bourns")
        (field (name "MANUFACTURER PART NUMBER") "CR0805-FX-3000ELF")
      )
      (libsource (lib "Kish Spark") (part "RC0805FR-1018KL (2)"))
    )
    (comp (ref "R37")
      (value "10k")
      (footprint "R0603")
      (description "Res Thick Film 0603 10K Ohm 5% 1/10W 200ppm/C Molded SMD SMD Paper T/R")
      (fields
        (field (name "TOLERANCE") "5%")
        (field (name "Comment") "CRCW060310K0JNEA")
        (field (name "SOURCE") "PTZLib.SchLib")
      )
      (libsource (lib "Kish Spark") (part "RN73R1JTTD3302F10"))
    )
    (comp (ref "R38")
      (value "8.2k")
      (footprint "0805")
      (description "Res Thick Film 0805 8.2K Ohm 5% 1/8W ±200ppm/°C Molded SMD SMD Paper T/R")
      (fields
        (field (name "MANUFACTURER") "Vishay Dale")
        (field (name "MANUFACTURER PART NUMBER") "CRCW08058K20JNEA")
      )
      (libsource (lib "Kish Spark") (part "RC0805FR-1018KL (2)"))
    )
    (comp (ref "R39")
      (value "1.2k")
      (footprint "0805")
      (description "Res Thick Film 0805 1.2K Ohm 1% 0.125W(1/8W) ±100ppm/C Molded SMD Paper Tape on Plastic Reel")
      (fields
        (field (name "MANUFACTURER") "Bourns")
        (field (name "MANUFACTURER PART NUMBER") "CR0805-FX-1201ELF")
      )
      (libsource (lib "Kish Spark") (part "RC0805FR-1018KL (2)"))
    )
    (comp (ref "R40")
      (value "2.7k")
      (footprint "0805")
      (description "Res Thick Film 0805 2.7K Ohm 1% 1/8W ±100ppm/°C Molded SMD SMD Paper Tape on Plastic Reel")
      (fields
        (field (name "MANUFACTURER") "Bourns")
        (field (name "MANUFACTURER PART NUMBER") "CR0805-FX-2701ELF")
      )
      (libsource (lib "Kish Spark") (part "RC0805FR-1018KL (2)"))
    )
    (comp (ref "R41")
      (value "470k")
      (footprint "0805")
      (fields
        (field (name "MANUFACTURER") "TT Welwyn")
        (field (name "MANUFACTURER PART NUMBER") "WCR0805-470KFI")
        (field (name "Comment") "CMP-009-00316-1")
      )
      (libsource (lib "Kish Spark") (part "RC0805FR-1018KL (2)"))
    )
    (comp (ref "R42")
      (value "82k")
      (footprint "0805")
      (description "Res Thick Film 0805 82K Ohm 1% 1/8W ±100ppm/°C Molded SMD Paper T/R")
      (fields
        (field (name "MANUFACTURER") "Yageo")
        (field (name "MANUFACTURER PART NUMBER") "RC0805FR-0782KL")
      )
      (libsource (lib "Kish Spark") (part "RC0805FR-1018KL (2)"))
    )
    (comp (ref "R43")
      (value "1.8k")
      (footprint "0805")
      (description "Res Thick Film 0805 1.8K Ohm 5% 1/8W ±200ppm/°C Molded SMD SMD Paper T/R")
      (fields
        (field (name "MANUFACTURER") "Vishay Dale")
        (field (name "MANUFACTURER PART NUMBER") "CRCW08051K80JNEA")
      )
      (libsource (lib "Kish Spark") (part "RC0805FR-1018KL (2)"))
    )
    (comp (ref "R44")
      (value "20k")
      (footprint "BOUR-TC33X-2_V")
      (description "Res Trimmer 20K Ohm 25% 1/10W 1(Elec)/1(Mech)Turn (3 X 3.8mm) Foot Print SMD Embossed T/R")
      (fields (field (name "POWER") "100mW") (field (name "TOLERANCE") "25%"))
      (libsource (lib "Kish Spark") (part "RES-ADJ-3_A"))
    )
    (comp (ref "R45")
      (value "330k")
      (footprint "0805")
      (description "Res Thick Film 0805 330K Ohm 1% 1/8W ±100ppm/°C Molded SMD Paper T/R")
      (fields
        (field (name "MANUFACTURER") "Yageo")
        (field (name "MANUFACTURER PART NUMBER") "RC0805FR-07330KL")
      )
      (libsource (lib "Kish Spark") (part "RC0805FR-1018KL (2)"))
    )
    (comp (ref "R46")
      (value "82k")
      (footprint "0805")
      (description "Res Thick Film 0805 82K Ohm 1% 1/8W ±100ppm/°C Molded SMD Paper T/R")
      (fields
        (field (name "MANUFACTURER") "Yageo")
        (field (name "MANUFACTURER PART NUMBER") "RC0805FR-0782KL")
      )
      (libsource (lib "Kish Spark") (part "RC0805FR-1018KL (2)"))
    )
    (comp (ref "R47")
      (value "10k")
      (footprint "R0603")
      (description "Res Thick Film 0603 10K Ohm 5% 1/10W 200ppm/C Molded SMD SMD Paper T/R")
      (fields
        (field (name "TOLERANCE") "5%")
        (field (name "Comment") "CRCW060310K0JNEA")
        (field (name "SOURCE") "PTZLib.SchLib")
      )
      (libsource (lib "Kish Spark") (part "RN73R1JTTD3302F10"))
    )
    (comp (ref "R48")
      (value "12k")
      (footprint "0805")
      (description "Res Thick Film 0805 12K Ohm 1% 0.125W(1/8W) ±100ppm/C Pad SMD T/R")
      (fields
        (field (name "MANUFACTURER") "Yageo")
        (field (name "MANUFACTURER PART NUMBER") "RC0805FR-0712KL")
      )
      (libsource (lib "Kish Spark") (part "RC0805FR-1018KL (2)"))
    )
    (comp (ref "R49")
      (value "10k")
      (footprint "R0603")
      (description "Res Thick Film 0603 10K Ohm 5% 1/10W 200ppm/C Molded SMD SMD Paper T/R")
      (fields
        (field (name "TOLERANCE") "5%")
        (field (name "Comment") "CRCW060310K0JNEA")
        (field (name "SOURCE") "PTZLib.SchLib")
      )
      (libsource (lib "Kish Spark") (part "RN73R1JTTD3302F10"))
    )
    (comp (ref "R50")
      (value "18k")
      (footprint "R0805")
      (description "Res Thick Film 0805 18K Ohm 1% 1/8W ±100ppm/°C Molded SMD SMD Paper T/R")
      (fields
        (field (name "MANUFACTURER") "Yageo")
        (field (name "MANUFACTURER PART NUMBER") "RC0805FR-1018KL")
      )
      (libsource (lib "Kish Spark") (part "RES-2"))
    )
    (comp (ref "R51")
      (value "18k")
      (footprint "R0805")
      (description "Res Thick Film 0805 18K Ohm 1% 1/8W ±100ppm/°C Molded SMD SMD Paper T/R")
      (fields
        (field (name "MANUFACTURER") "Yageo")
        (field (name "MANUFACTURER PART NUMBER") "RC0805FR-1018KL")
      )
      (libsource (lib "Kish Spark") (part "RES-2"))
    )
    (comp (ref "R52")
      (value "20k")
      (footprint "BOUR-TC33X-2_V")
      (description "Res Trimmer 20K Ohm 25% 1/10W 1(Elec)/1(Mech)Turn (3 X 3.8mm) Foot Print SMD Embossed T/R")
      (fields (field (name "POWER") "100mW") (field (name "TOLERANCE") "25%"))
      (libsource (lib "Kish Spark") (part "RES-ADJ-3_A"))
    )
    (comp (ref "R53")
      (value "1 M")
      (footprint "0805")
      (description "Res Thick Film 0805 1M Ohm 5% 0.125W(1/8W) ±200ppm/°C Pad SMD T/R")
      (fields
        (field (name "MANUFACTURER") "Vishay")
        (field (name "MANUFACTURER PART NUMBER") "CRCW08051M00JNEAC")
      )
      (libsource (lib "Kish Spark") (part "RC0805FR-1018KL (2)"))
    )
    (comp (ref "R54")
      (value "1 M")
      (footprint "0805")
      (description "Res Thick Film 0805 1M Ohm 5% 0.125W(1/8W) ±200ppm/°C Pad SMD T/R")
      (fields
        (field (name "MANUFACTURER") "Vishay")
        (field (name "MANUFACTURER PART NUMBER") "CRCW08051M00JNEAC")
      )
      (libsource (lib "Kish Spark") (part "RC0805FR-1018KL (2)"))
    )
    (comp (ref "R55")
      (value "680")
      (footprint "R0805")
      (description "CRCW Thick Film Commodity Chip Resistor 0805 Size 680 Ohm 5% 0.125 W 200 ppm/K 2-Pin SMD Paper T/R")
      (fields
        (field (name "MANUFACTURER") "Vishay")
        (field (name "MANUFACTURER PART NUMBER") "CRCW0805680RJNEBC")
      )
      (libsource (lib "Kish Spark") (part "RC0805FR-1018KL (2)"))
    )
    (comp (ref "R56")
      (value "0")
      (footprint "R0603")
      (description "Res Thkflm 0603 0 Ohm Jumper 1/10W 100Ppm/ C Smd Rohs Compliant: Yes")
      (fields (field (name "Comment") "RMCF0603ZT0R00") (field (name "SOURCE") "PTZLib.SchLib"))
      (libsource (lib "Kish Spark") (part "CRCW060349R9FKEAC"))
    )
    (comp (ref "R57")
      (value "0")
      (footprint "0805")
      (description "RC Series 0805 0.125 W 0 Ohm Jumper SMT Thick Film Chip Resistor")
      (fields
        (field (name "MANUFACTURER") "Yageo")
        (field (name "MANUFACTURER PART NUMBER") "RC0805FR-070RL")
      )
      (libsource (lib "Kish Spark") (part "RC0805FR-1018KL (2)"))
    )
    (comp (ref "R58")
      (value "0")
      (footprint "R0603")
      (description "Res Thkflm 0603 0 Ohm Jumper 1/10W 100Ppm/ C Smd Rohs Compliant: Yes")
      (fields (field (name "Comment") "RMCF0603ZT0R00") (field (name "SOURCE") "PTZLib.SchLib"))
      (libsource (lib "Kish Spark") (part "CRCW060349R9FKEAC"))
    )
    (comp (ref "R59")
      (value "10")
      (footprint "R0603")
      (description "Res Thick Film 0603 10K Ohm 5% 1/10W 200ppm/C Molded SMD SMD Paper T/R")
      (fields (field (name "TOLERANCE") "1%") (field (name "MANUFACTURER") "Vishay Dale"))
      (libsource (lib "Kish Spark") (part "RES-2"))
    )
    (comp (ref "R60")
      (value "10")
      (footprint "R0603")
      (description "Res Thick Film 0603 10K Ohm 5% 1/10W 200ppm/C Molded SMD SMD Paper T/R")
      (fields (field (name "TOLERANCE") "1%") (field (name "MANUFACTURER") "Vishay Dale"))
      (libsource (lib "Kish Spark") (part "RES-2"))
    )
    (comp (ref "R61")
      (value "10")
      (footprint "R0603")
      (description "Res Thick Film 0603 10K Ohm 5% 1/10W 200ppm/C Molded SMD SMD Paper T/R")
      (fields (field (name "TOLERANCE") "1%") (field (name "MANUFACTURER") "Vishay Dale"))
      (libsource (lib "Kish Spark") (part "RES-2"))
    )
    (comp (ref "R62")
      (value "1.5M")
      (footprint "0805")
      (description "Thick Film Resistors 1.5M 5%")
      (fields
        (field (name "MANUFACTURER") "Bourns")
        (field (name "MANUFACTURER PART NUMBER") "CR0805-JW-155ELF")
      )
      (libsource (lib "Kish Spark") (part "RC0805FR-1018KL (2)"))
    )
    (comp (ref "R63")
      (value "18k")
      (footprint "R0805")
      (description "Res Thick Film 0805 18K Ohm 1% 1/8W ±100ppm/°C Molded SMD SMD Paper T/R")
      (fields
        (field (name "MANUFACTURER") "Yageo")
        (field (name "MANUFACTURER PART NUMBER") "RC0805FR-1018KL")
      )
      (libsource (lib "Kish Spark") (part "RES-2"))
    )
    (comp (ref "R64")
      (value "47k")
      (footprint "0805")
      (description "High Precision-High Stability Chip Resistor Thin Film 0805 47kOhm 1% Paper T/R")
      (fields
        (field (name "MANUFACTURER") "Yageo")
        (field (name "MANUFACTURER PART NUMBER") "RT0805FRE0747KL")
      )
      (libsource (lib "Kish Spark") (part "RC0805FR-1018KL (2)"))
    )
    (comp (ref "R65")
      (value "0")
      (footprint "R0603")
      (description "Res Thkflm 0603 0 Ohm Jumper 1/10W 100Ppm/ C Smd Rohs Compliant: Yes")
      (fields (field (name "Comment") "RMCF0603ZT0R00") (field (name "SOURCE") "PTZLib.SchLib"))
      (libsource (lib "Kish Spark") (part "CRCW060349R9FKEAC"))
    )
    (comp (ref "R66")
      (value "330k")
      (footprint "0805")
      (description "Res Thick Film 0805 330K Ohm 1% 1/8W ±100ppm/°C Molded SMD Paper T/R")
      (fields
        (field (name "MANUFACTURER") "Yageo")
        (field (name "MANUFACTURER PART NUMBER") "RC0805FR-07330KL")
      )
      (libsource (lib "Kish Spark") (part "RC0805FR-1018KL (2)"))
    )
    (comp (ref "R67")
      (value "330k")
      (footprint "0805")
      (description "Res Thick Film 0805 330K Ohm 1% 1/8W ±100ppm/°C Molded SMD Paper T/R")
      (fields
        (field (name "MANUFACTURER") "Yageo")
        (field (name "MANUFACTURER PART NUMBER") "RC0805FR-07330KL")
      )
      (libsource (lib "Kish Spark") (part "RC0805FR-1018KL (2)"))
    )
    (comp (ref "R68")
      (value "0")
      (footprint "R0603")
      (description "Res Thkflm 0603 0 Ohm Jumper 1/10W 100Ppm/ C Smd Rohs Compliant: Yes")
      (fields (field (name "Comment") "RMCF0603ZT0R00") (field (name "SOURCE") "PTZLib.SchLib"))
      (libsource (lib "Kish Spark") (part "CRCW060349R9FKEAC"))
    )
    (comp (ref "R69")
      (value "2.2k")
      (footprint "0805")
      (description "anti-surge endured pulse power thick film chip resistor, 0805, RoHS")
      (fields
        (field (name "MANUFACTURER") "KOA Speer")
        (field (name "MANUFACTURER PART NUMBER") "SG73P2ATTD222J")
      )
      (libsource (lib "Kish Spark") (part "RC0805FR-1018KL (2)"))
    )
    (comp (ref "R70")
      (value "2.2k")
      (footprint "0805")
      (description "Res Thick Film 0805 2.2K Ohm 5% 1/8W ±200ppm/°C Molded SMD SMD Paper Tape on Plastic Reel")
      (fields
        (field (name "MANUFACTURER") "Bourns")
        (field (name "MANUFACTURER PART NUMBER") "CR0805-JW-222ELF")
      )
      (libsource (lib "Kish Spark") (part "RC0805FR-1018KL (2)"))
    )
    (comp (ref "R71")
      (value "390k")
      (footprint "R0805")
      (description "Chip Resistor Precision Grade Thick Film 0805 390kOhm 1% Paper T/R")
      (fields (field (name "TOLERANCE") "1%") (field (name "Comment") "CMP-009-00320-1"))
      (libsource (lib "Kish Spark") (part "RES-2"))
    )
    (comp (ref "R72")
      (value "330k")
      (footprint "0805")
      (description "Res Thick Film 0805 330K Ohm 1% 1/8W ±100ppm/°C Molded SMD Paper T/R")
      (fields
        (field (name "MANUFACTURER") "Yageo")
        (field (name "MANUFACTURER PART NUMBER") "RC0805FR-07330KL")
      )
      (libsource (lib "Kish Spark") (part "RC0805FR-1018KL (2)"))
    )
    (comp (ref "R73")
      (value "10k")
      (footprint "R0603")
      (description "Res Thick Film 0603 10K Ohm 5% 1/10W 200ppm/C Molded SMD SMD Paper T/R")
      (fields
        (field (name "TOLERANCE") "5%")
        (field (name "Comment") "CRCW060310K0JNEA")
        (field (name "SOURCE") "PTZLib.SchLib")
      )
      (libsource (lib "Kish Spark") (part "RN73R1JTTD3302F10"))
    )
    (comp (ref "R74")
      (value "510k")
      (footprint "0805")
      (description "Res Thick Film 0805 510K Ohm 1% 1/8W +/-100ppm/ßC Molded SMD Paper T/R")
      (fields
        (field (name "MANUFACTURER") "Yageo")
        (field (name "MANUFACTURER PART NUMBER") "RC0805FR-07510KL")
      )
      (libsource (lib "Kish Spark") (part "RC0805FR-1018KL (2)"))
    )
    (comp (ref "R75")
      (value "0")
      (footprint "R0603")
      (description "Res Thkflm 0603 0 Ohm Jumper 1/10W 100Ppm/ C Smd Rohs Compliant: Yes")
      (fields (field (name "Comment") "RMCF0603ZT0R00") (field (name "SOURCE") "PTZLib.SchLib"))
      (libsource (lib "Kish Spark") (part "CRCW060349R9FKEAC"))
    )
    (comp (ref "R76")
      (value "1.2k")
      (footprint "0805")
      (description "Res Thick Film 0805 1.2K Ohm 1% 0.125W(1/8W) ±100ppm/C Molded SMD Paper Tape on Plastic Reel")
      (fields
        (field (name "MANUFACTURER") "Bourns")
        (field (name "MANUFACTURER PART NUMBER") "CR0805-FX-1201ELF")
      )
      (libsource (lib "Kish Spark") (part "RC0805FR-1018KL (2)"))
    )
    (comp (ref "R77")
      (value "0")
      (footprint "R0603")
      (description "Res Thkflm 0603 0 Ohm Jumper 1/10W 100Ppm/ C Smd Rohs Compliant: Yes")
      (fields (field (name "Comment") "RMCF0603ZT0R00") (field (name "SOURCE") "PTZLib.SchLib"))
      (libsource (lib "Kish Spark") (part "CRCW060349R9FKEAC"))
    )
    (comp (ref "R78")
      (value "200")
      (footprint "0805")
      (description "Res Thick Film 0805 200 Ohm 1% 1/8W ±100ppm/°C Molded SMD SMD Paper Tape on Plastic Reel")
      (fields
        (field (name "MANUFACTURER") "Bourns")
        (field (name "MANUFACTURER PART NUMBER") "CR0805-FX-2000ELF")
      )
      (libsource (lib "Kish Spark") (part "RC0805FR-1018KL (2)"))
    )
    (comp (ref "R79")
      (value "1.2k")
      (footprint "0805")
      (description "Res Thick Film 0805 1.2K Ohm 1% 0.125W(1/8W) ±100ppm/C Molded SMD Paper Tape on Plastic Reel")
      (fields
        (field (name "MANUFACTURER") "Bourns")
        (field (name "MANUFACTURER PART NUMBER") "CR0805-FX-1201ELF")
      )
      (libsource (lib "Kish Spark") (part "RC0805FR-1018KL (2)"))
    )
    (comp (ref "R80")
      (value "13")
      (footprint "0805")
      (description "Res Thick Film 0805 13 Ohm 1% 1/8W ±100ppm/°C Molded SMD SMD Paper Tape on Plastic Reel")
      (fields
        (field (name "MANUFACTURER") "Bourns")
        (field (name "MANUFACTURER PART NUMBER") "CR0805-FX-13R0ELF")
      )
      (libsource (lib "Kish Spark") (part "CR0805-FX-13R0ELF"))
    )
    (comp (ref "R81")
      (value "12k")
      (footprint "0805")
      (description "Res Thick Film 0805 12K Ohm 1% 0.125W(1/8W) ±100ppm/C Pad SMD T/R")
      (fields
        (field (name "MANUFACTURER") "Yageo")
        (field (name "MANUFACTURER PART NUMBER") "RC0805FR-0712KL")
      )
      (libsource (lib "Kish Spark") (part "RC0805FR-1018KL (2)"))
    )
    (comp (ref "R82")
      (value "390k")
      (footprint "R0805")
      (description "Chip Resistor Precision Grade Thick Film 0805 390kOhm 1% Paper T/R")
      (fields (field (name "TOLERANCE") "1%") (field (name "Comment") "CMP-009-00320-1"))
      (libsource (lib "Kish Spark") (part "RES-2"))
    )
    (comp (ref "R83")
      (value "390k")
      (footprint "R0805")
      (description "Chip Resistor Precision Grade Thick Film 0805 390kOhm 1% Paper T/R")
      (fields (field (name "TOLERANCE") "1%") (field (name "Comment") "CMP-009-00320-1"))
      (libsource (lib "Kish Spark") (part "RES-2"))
    )
    (comp (ref "R84")
      (value "12k")
      (footprint "0805")
      (description "Res Thick Film 0805 12K Ohm 1% 0.125W(1/8W) ±100ppm/C Pad SMD T/R")
      (fields
        (field (name "MANUFACTURER") "Yageo")
        (field (name "MANUFACTURER PART NUMBER") "RC0805FR-0712KL")
      )
      (libsource (lib "Kish Spark") (part "RC0805FR-1018KL (2)"))
    )
    (comp (ref "R85")
      (value "390k")
      (footprint "R0805")
      (description "Chip Resistor Precision Grade Thick Film 0805 390kOhm 1% Paper T/R")
      (fields (field (name "TOLERANCE") "1%") (field (name "Comment") "CMP-009-00320-1"))
      (libsource (lib "Kish Spark") (part "RES-2"))
    )
    (comp (ref "R86")
      (value "10k")
      (footprint "R0603")
      (description "Res Thick Film 0603 10K Ohm 5% 1/10W 200ppm/C Molded SMD SMD Paper T/R")
      (fields
        (field (name "TOLERANCE") "5%")
        (field (name "Comment") "CRCW060310K0JNEA")
        (field (name "SOURCE") "PTZLib.SchLib")
      )
      (libsource (lib "Kish Spark") (part "RN73R1JTTD3302F10"))
    )
    (comp (ref "R87")
      (value "390k")
      (footprint "R0805")
      (description "Chip Resistor Precision Grade Thick Film 0805 390kOhm 1% Paper T/R")
      (fields (field (name "TOLERANCE") "1%") (field (name "Comment") "CMP-009-00320-1"))
      (libsource (lib "Kish Spark") (part "RES-2"))
    )
    (comp (ref "R88")
      (value "0")
      (footprint "R0603")
      (description "Res Thkflm 0603 0 Ohm Jumper 1/10W 100Ppm/ C Smd Rohs Compliant: Yes")
      (fields (field (name "Comment") "RMCF0603ZT0R00") (field (name "SOURCE") "PTZLib.SchLib"))
      (libsource (lib "Kish Spark") (part "CRCW060349R9FKEAC"))
    )
    (comp (ref "TP6")
      (value "5003")
      (footprint "KSTN-5003")
      (description "Test Point, Orange, Height 4.6 mm, Tail Length 3 mm, 1-Pin THD, RoHS")
      (fields (field (name "MANUFACTURER") "Keystone"))
      (libsource (lib "Kish Spark") (part "TESTPOINT_ORANGE"))
    )
    (comp (ref "TP7")
      (value "5003")
      (footprint "KSTN-5003")
      (description "Test Point, Orange, Height 4.6 mm, Tail Length 3 mm, 1-Pin THD, RoHS")
      (fields (field (name "MANUFACTURER") "Keystone"))
      (libsource (lib "Kish Spark") (part "TESTPOINT_ORANGE"))
    )
    (comp (ref "TP8")
      (value "5003")
      (footprint "KSTN-5003")
      (description "Test Point, Orange, Height 4.6 mm, Tail Length 3 mm, 1-Pin THD, RoHS")
      (fields (field (name "MANUFACTURER") "Keystone"))
      (libsource (lib "Kish Spark") (part "TESTPOINT_ORANGE"))
    )
    (comp (ref "TP9")
      (value "5003")
      (footprint "KSTN-5003")
      (description "Test Point, Orange, Height 4.6 mm, Tail Length 3 mm, 1-Pin THD, RoHS")
      (fields (field (name "MANUFACTURER") "Keystone"))
      (libsource (lib "Kish Spark") (part "TESTPOINT_ORANGE"))
    )
    (comp (ref "TP10")
      (value "5003")
      (footprint "KSTN-5003")
      (description "Test Point, Orange, Height 4.6 mm, Tail Length 3 mm, 1-Pin THD, RoHS")
      (fields (field (name "MANUFACTURER") "Keystone"))
      (libsource (lib "Kish Spark") (part "TESTPOINT_ORANGE"))
    )
    (comp (ref "TP11")
      (value "5003")
      (footprint "KSTN-5003")
      (description "Test Point, Orange, Height 4.6 mm, Tail Length 3 mm, 1-Pin THD, RoHS")
      (fields (field (name "MANUFACTURER") "Keystone"))
      (libsource (lib "Kish Spark") (part "TESTPOINT_ORANGE"))
    )
    (comp (ref "TP12")
      (value "5003")
      (footprint "KSTN-5003")
      (description "Test Point, Orange, Height 4.6 mm, Tail Length 3 mm, 1-Pin THD, RoHS")
      (fields (field (name "MANUFACTURER") "Keystone"))
      (libsource (lib "Kish Spark") (part "TESTPOINT_ORANGE"))
    )
    (comp (ref "TP13")
      (value "5003")
      (footprint "KSTN-5003")
      (description "Test Point, Orange, Height 4.6 mm, Tail Length 3 mm, 1-Pin THD, RoHS")
      (fields (field (name "MANUFACTURER") "Keystone"))
      (libsource (lib "Kish Spark") (part "TESTPOINT_ORANGE"))
    )
    (comp (ref "TP14")
      (value "5003")
      (footprint "KSTN-5003")
      (description "Test Point, Orange, Height 4.6 mm, Tail Length 3 mm, 1-Pin THD, RoHS")
      (fields (field (name "MANUFACTURER") "Keystone"))
      (libsource (lib "Kish Spark") (part "TESTPOINT_ORANGE"))
    )
    (comp (ref "TP15")
      (value "5003")
      (footprint "KSTN-5003")
      (description "Test Point, Orange, Height 4.6 mm, Tail Length 3 mm, 1-Pin THD, RoHS")
      (fields (field (name "MANUFACTURER") "Keystone"))
      (libsource (lib "Kish Spark") (part "TESTPOINT_ORANGE"))
    )
    (comp (ref "TP16")
      (value "5003")
      (footprint "KSTN-5003")
      (description "Test Point, Orange, Height 4.6 mm, Tail Length 3 mm, 1-Pin THD, RoHS")
      (fields (field (name "MANUFACTURER") "Keystone"))
      (libsource (lib "Kish Spark") (part "TESTPOINT_ORANGE"))
    )
    (comp (ref "TP17")
      (value "5003")
      (footprint "KSTN-5003")
      (description "Test Point, Orange, Height 4.6 mm, Tail Length 3 mm, 1-Pin THD, RoHS")
      (fields (field (name "MANUFACTURER") "Keystone"))
      (libsource (lib "Kish Spark") (part "TESTPOINT_ORANGE"))
    )
    (comp (ref "TP18")
      (value "5003")
      (footprint "KSTN-5003")
      (description "Test Point, Orange, Height 4.6 mm, Tail Length 3 mm, 1-Pin THD, RoHS")
      (fields (field (name "MANUFACTURER") "Keystone"))
      (libsource (lib "Kish Spark") (part "TESTPOINT_ORANGE"))
    )
    (comp (ref "TP19")
      (value "5003")
      (footprint "KSTN-5003")
      (description "Test Point, Orange, Height 4.6 mm, Tail Length 3 mm, 1-Pin THD, RoHS")
      (fields (field (name "MANUFACTURER") "Keystone"))
      (libsource (lib "Kish Spark") (part "TESTPOINT_ORANGE"))
    )
    (comp (ref "TP20")
      (value "5003")
      (footprint "KSTN-5003")
      (description "Test Point, Orange, Height 4.6 mm, Tail Length 3 mm, 1-Pin THD, RoHS")
      (fields (field (name "MANUFACTURER") "Keystone"))
      (libsource (lib "Kish Spark") (part "TESTPOINT_ORANGE"))
    )
    (comp (ref "U6")
      (value "AS2523-T")
      (footprint "AS2523")
      (description "AS Series 3 to 5 V Telephone Line Interface and Speakerphone Circuit - SOIC-28")
      (libsource (lib "Kish Spark") (part "AS2523T"))
    )
    (comp (ref "U7")
      (value "PC817XI")
      (footprint "SOIC254P975X460-4N")
      (description "OPTOISOLATOR 5KV TRANS 4SMD")
      (fields (field (name "MF") "Sharp Microelectronics"))
      (libsource (lib "Kish Spark") (part "PC817XI"))
    )
    (comp (ref "U8")
      (value "BA8206F-E2")
      (footprint "BA8206")
      (description "BA8206 Series 14 to 18 V 450 mW Tone Ringer IC for Telephone Set - SOIC-8")
      (fields (field (name "MANUFACTURER") "Rohm"))
      (libsource (lib "Kish Spark") (part "BA8206F-E2"))
    )
  )
  (nets
    (net (code "1") (name "+3V3") (class "Default")
      (node (ref "R47") (pin "2") (pinfunction "2_2") (pintype "passive"))
    )
    (net (code "2") (name "/AGND") (class "Default")
      (node (ref "C48") (pin "2") (pinfunction "2_2") (pintype "passive"))
      (node (ref "R82") (pin "2") (pinfunction "2_2") (pintype "passive"))
      (node (ref "U6") (pin "19") (pinfunction "AGND_19") (pintype "passive"))
    )
    (net (code "3") (name "/BUZZER1") (class "Default")
      (node (ref "C53") (pin "2") (pinfunction "2_2") (pintype "passive"))
    )
    (net (code "4") (name "/BUZZER2") (class "Default")
      (node (ref "C54") (pin "1") (pinfunction "1_1") (pintype "passive"))
      (node (ref "C55") (pin "1") (pinfunction "1_1") (pintype "passive"))
      (node (ref "C56") (pin "2") (pinfunction "2_2") (pintype "passive"))
      (node (ref "D11") (pin "3") (pinfunction "NEG_3") (pintype "passive"))
      (node (ref "D12") (pin "2") (pinfunction "2_2") (pintype "passive"))
      (node (ref "R72") (pin "1") (pinfunction "1_1") (pintype "passive"))
      (node (ref "R73") (pin "1") (pinfunction "1_1") (pintype "passive"))
      (node (ref "R75") (pin "2") (pinfunction "2_2") (pintype "passive"))
      (node (ref "U8") (pin "5") (pinfunction "GND_5") (pintype "passive"))
    )
    (net (code "5") (name "/CLK{slash}HFI") (class "Default")
      (node (ref "C46") (pin "2") (pinfunction "2_2") (pintype "passive"))
      (node (ref "R61") (pin "2") (pinfunction "2_2") (pintype "passive"))
      (node (ref "TP18") (pin "1") (pinfunction "1_1") (pintype "passive"))
    )
    (net (code "6") (name "/DETI") (class "Default")
      (node (ref "R68") (pin "1") (pinfunction "1_1") (pintype "passive"))
    )
    (net (code "7") (name "/DI{slash}xPD") (class "Default")
      (node (ref "C45") (pin "2") (pinfunction "2_2") (pintype "passive"))
      (node (ref "R60") (pin "2") (pinfunction "2_2") (pintype "passive"))
      (node (ref "TP17") (pin "1") (pinfunction "1_1") (pintype "passive"))
    )
    (net (code "8") (name "/DPN") (class "Default")
      (node (ref "R46") (pin "1") (pinfunction "1_1") (pintype "passive"))
    )
    (net (code "9") (name "/FCI") (class "Default")
      (node (ref "R47") (pin "1") (pinfunction "1_1") (pintype "passive"))
      (node (ref "TP14") (pin "1") (pinfunction "1_1") (pintype "passive"))
      (node (ref "U7") (pin "4") (pinfunction "CT_4") (pintype "passive"))
    )
    (net (code "10") (name "/HF") (class "Default")
      (node (ref "D5") (pin "2") (pinfunction "A_2") (pintype "passive"))
      (node (ref "R54") (pin "2") (pinfunction "2_2") (pintype "passive"))
    )
    (net (code "11") (name "/HF_MIC1") (class "Default")
      (node (ref "C24") (pin "2") (pinfunction "2_2") (pintype "passive"))
      (node (ref "R29") (pin "1") (pinfunction "1_1") (pintype "passive"))
      (node (ref "R33") (pin "2") (pinfunction "2_2") (pintype "passive"))
    )
    (net (code "12") (name "/HF_MIC2") (class "Default")
      (node (ref "C28") (pin "1") (pinfunction "1_1") (pintype "passive"))
      (node (ref "J5") (pin "1") (pinfunction "1_1") (pintype "passive"))
      (node (ref "J5") (pin "2") (pinfunction "2_2") (pintype "passive"))
      (node (ref "R35") (pin "2") (pinfunction "2_2") (pintype "passive"))
    )
    (net (code "13") (name "/HS") (class "Default")
      (node (ref "D6") (pin "2") (pinfunction "A_2") (pintype "passive"))
      (node (ref "R53") (pin "2") (pinfunction "2_2") (pintype "passive"))
    )
    (net (code "14") (name "/HS_2") (class "Default")
      (node (ref "D2") (pin "1") (pinfunction "POS_1") (pintype "passive"))
      (node (ref "Q4") (pin "1") (pinfunction "E_1") (pintype "passive"))
      (node (ref "R34") (pin "1") (pinfunction "1_1") (pintype "passive"))
      (node (ref "R62") (pin "1") (pinfunction "1_1") (pintype "passive"))
    )
    (net (code "15") (name "/HS_MIC1") (class "Default")
      (node (ref "C29") (pin "2") (pinfunction "2_2") (pintype "passive"))
      (node (ref "R30") (pin "1") (pinfunction "1_1") (pintype "passive"))
      (node (ref "R38") (pin "2") (pinfunction "2_2") (pintype "passive"))
    )
    (net (code "16") (name "/HS_MIC2") (class "Default")
      (node (ref "C32") (pin "2") (pinfunction "2_2") (pintype "passive"))
      (node (ref "R38") (pin "1") (pinfunction "1_1") (pintype "passive"))
      (node (ref "R39") (pin "2") (pinfunction "2_2") (pintype "passive"))
    )
    (net (code "17") (name "/HS_SP1") (class "Default")
      (node (ref "J9") (pin "3") (pinfunction "3_3") (pintype "passive"))
    )
    (net (code "18") (name "/LN_O") (class "Default")
      (node (ref "C57") (pin "1") (pinfunction "1_1") (pintype "passive"))
      (node (ref "Q12") (pin "2") (pinfunction "E_2") (pintype "passive"))
      (node (ref "Q4") (pin "3") (pinfunction "C_3") (pintype "passive"))
      (node (ref "Q5") (pin "3") (pinfunction "C_3") (pintype "passive"))
      (node (ref "R28") (pin "1") (pinfunction "1_1") (pintype "passive"))
      (node (ref "R80") (pin "1") (pinfunction "1_1") (pintype "passive"))
    )
    (net (code "19") (name "/LS") (class "Default")
      (node (ref "C23") (pin "2") (pinfunction "2_2") (pintype "passive"))
      (node (ref "D4") (pin "C") (pinfunction "K_C") (pintype "passive"))
      (node (ref "J3") (pin "2") (pinfunction "2_2") (pintype "passive"))
      (node (ref "R28") (pin "2") (pinfunction "2_2") (pintype "passive"))
      (node (ref "R31") (pin "2") (pinfunction "2_2") (pintype "passive"))
      (node (ref "R77") (pin "2") (pinfunction "2_2") (pintype "passive"))
      (node (ref "TP8") (pin "1") (pinfunction "1_1") (pintype "passive"))
      (node (ref "U6") (pin "15") (pinfunction "LS_15") (pintype "passive"))
    )
    (net (code "20") (name "/M1") (class "Default")
      (node (ref "C29") (pin "1") (pinfunction "1_1") (pintype "passive"))
      (node (ref "C31") (pin "2") (pinfunction "2_2") (pintype "passive"))
      (node (ref "C63") (pin "2") (pinfunction "2_2") (pintype "passive"))
      (node (ref "U6") (pin "8") (pinfunction "M1_8") (pintype "passive"))
    )
    (net (code "21") (name "/M2") (class "Default")
      (node (ref "C31") (pin "1") (pinfunction "1_1") (pintype "passive"))
      (node (ref "C32") (pin "1") (pinfunction "1_1") (pintype "passive"))
      (node (ref "C62") (pin "2") (pinfunction "2_2") (pintype "passive"))
      (node (ref "U6") (pin "6") (pinfunction "M2_6") (pintype "passive"))
    )
    (net (code "22") (name "/P14_DS") (class "Default")
      (node (ref "J6") (pin "1") (pinfunction "1_1") (pintype "passive"))
      (node (ref "R43") (pin "2") (pinfunction "2_2") (pintype "passive"))
    )
    (net (code "23") (name "/P16_DS") (class "Default")
      (node (ref "C68") (pin "2") (pinfunction "2_2") (pintype "passive"))
      (node (ref "J10") (pin "3") (pinfunction "3_3") (pintype "passive"))
      (node (ref "R81") (pin "1") (pinfunction "1_1") (pintype "passive"))
      (node (ref "R84") (pin "2") (pinfunction "2_2") (pintype "passive"))
    )
    (net (code "24") (name "/P17_DS") (class "Default")
      (node (ref "C58") (pin "2") (pinfunction "2_2") (pintype "passive"))
      (node (ref "J7") (pin "1") (pinfunction "1_1") (pintype "passive"))
      (node (ref "J8") (pin "1") (pinfunction "1_1") (pintype "passive"))
      (node (ref "R81") (pin "2") (pinfunction "2_2") (pintype "passive"))
    )
    (net (code "25") (name "/P18_DS") (class "Default")
      (node (ref "C59") (pin "1") (pinfunction "1_1") (pintype "passive"))
      (node (ref "J9") (pin "1") (pinfunction "1_1") (pintype "passive"))
      (node (ref "R78") (pin "2") (pinfunction "2_2") (pintype "passive"))
    )
    (net (code "26") (name "/P21_DS") (class "Default")
      (node (ref "C69") (pin "1") (pinfunction "1_1") (pintype "passive"))
      (node (ref "J12") (pin "1") (pinfunction "1_1") (pintype "passive"))
    )
    (net (code "27") (name "/RING") (class "Default")
      (node (ref "C65") (pin "2") (pinfunction "2_2") (pintype "passive"))
      (node (ref "D3") (pin "1") (pinfunction "1_1") (pintype "passive"))
      (node (ref "R32") (pin "1") (pinfunction "1_1") (pintype "passive"))
      (node (ref "TP9") (pin "1") (pinfunction "1_1") (pintype "passive"))
    )
    (net (code "28") (name "/RO") (class "Default")
      (node (ref "C60") (pin "2") (pinfunction "2_2") (pintype "passive"))
      (node (ref "J8") (pin "2") (pinfunction "2_2") (pintype "passive"))
      (node (ref "R44") (pin "1") (pinfunction "1_1") (pintype "passive"))
      (node (ref "R52") (pin "1") (pinfunction "1_1") (pintype "passive"))
      (node (ref "U6") (pin "17") (pinfunction "RO_17") (pintype "passive"))
    )
    (net (code "29") (name "/Rx_offset") (class "Default")
      (node (ref "C38") (pin "1") (pinfunction "1_1") (pintype "passive"))
      (node (ref "R83") (pin "1") (pinfunction "1_1") (pintype "passive"))
      (node (ref "U6") (pin "21") (pinfunction "RECV1_21") (pintype "passive"))
    )
    (net (code "30") (name "/SP1") (class "Default")
      (node (ref "R56") (pin "2") (pinfunction "2_2") (pintype "passive"))
    )
    (net (code "31") (name "/TIP") (class "Default")
      (node (ref "C64") (pin "2") (pinfunction "2_2") (pintype "passive"))
      (node (ref "D3") (pin "2") (pinfunction "2_2") (pintype "passive"))
      (node (ref "R26") (pin "1") (pinfunction "1_1") (pintype "passive"))
      (node (ref "TP7") (pin "1") (pinfunction "1_1") (pintype "passive"))
    )
    (net (code "32") (name "/TONE_IN") (class "Default")
      (node (ref "R25") (pin "1") (pinfunction "1_1") (pintype "passive"))
    )
    (net (code "33") (name "/TXO") (class "Default")
      (node (ref "J13") (pin "2") (pinfunction "2_2") (pintype "passive"))
      (node (ref "U6") (pin "3") (pinfunction "TXO_3") (pintype "passive"))
    )
    (net (code "34") (name "/TXV") (class "Default")
      (node (ref "J12") (pin "2") (pinfunction "2_2") (pintype "passive"))
      (node (ref "U6") (pin "4") (pinfunction "TXV_4") (pintype "passive"))
    )
    (net (code "35") (name "/xCS{slash}xMUTE") (class "Default")
      (node (ref "C44") (pin "2") (pinfunction "2_2") (pintype "passive"))
      (node (ref "R59") (pin "2") (pinfunction "2_2") (pintype "passive"))
      (node (ref "TP16") (pin "1") (pinfunction "1_1") (pintype "passive"))
    )
    (net (code "36") (name "GND") (class "Default")
      (node (ref "C19") (pin "2") (pinfunction "2_2") (pintype "passive"))
      (node (ref "C20") (pin "2") (pinfunction "2_2") (pintype "passive"))
      (node (ref "C21") (pin "2") (pinfunction "2_2") (pintype "passive"))
      (node (ref "C33") (pin "1") (pinfunction "1_1") (pintype "passive"))
      (node (ref "C35") (pin "1") (pinfunction "1_1") (pintype "passive"))
      (node (ref "C36") (pin "1") (pinfunction "1_1") (pintype "passive"))
      (node (ref "C39") (pin "1") (pinfunction "1_1") (pintype "passive"))
      (node (ref "C40") (pin "2") (pinfunction "2_2") (pintype "passive"))
      (node (ref "C43") (pin "2") (pinfunction "2_2") (pintype "passive"))
      (node (ref "C44") (pin "1") (pinfunction "1_1") (pintype "passive"))
      (node (ref "C45") (pin "1") (pinfunction "1_1") (pintype "passive"))
      (node (ref "C46") (pin "1") (pinfunction "1_1") (pintype "passive"))
      (node (ref "C48") (pin "1") (pinfunction "1_1") (pintype "passive"))
      (node (ref "C49") (pin "1") (pinfunction "1_1") (pintype "passive"))
      (node (ref "C50") (pin "2") (pinfunction "2_2") (pintype "passive"))
      (node (ref "C51") (pin "2") (pinfunction "2_2") (pintype "passive"))
      (node (ref "C52") (pin "1") (pinfunction "1_1") (pintype "passive"))
      (node (ref "C59") (pin "2") (pinfunction "2_2") (pintype "passive"))
      (node (ref "C60") (pin "1") (pinfunction "1_1") (pintype "passive"))
      (node (ref "C61") (pin "1") (pinfunction "1_1") (pintype "passive"))
      (node (ref "C62") (pin "1") (pinfunction "1_1") (pintype "passive"))
      (node (ref "C63") (pin "1") (pinfunction "1_1") (pintype "passive"))
      (node (ref "C64") (pin "1") (pinfunction "1_1") (pintype "passive"))
      (node (ref "C65") (pin "1") (pinfunction "1_1") (pintype "passive"))
      (node (ref "C68") (pin "1") (pinfunction "1_1") (pintype "passive"))
      (node (ref "D10") (pin "2") (pinfunction "2_2") (pintype "passive"))
      (node (ref "D2") (pin "3") (pinfunction "NEG_3") (pintype "passive"))
      (node (ref "D4") (pin "A") (pinfunction "A_A") (pintype "passive"))
      (node (ref "D9") (pin "2") (pinfunction "2_2") (pintype "passive"))
      (node (ref "J11") (pin "1") (pinfunction "1_1") (pintype "passive"))
      (node (ref "Q6") (pin "3") (pinfunction "C_3") (pintype "passive"))
      (node (ref "Q7") (pin "1") (pinfunction "E_1") (pintype "passive"))
      (node (ref "Q8") (pin "1") (pinfunction "E_1") (pintype "passive"))
      (node (ref "R27") (pin "3") (pinfunction "3_3") (pintype "passive"))
      (node (ref "R35") (pin "1") (pinfunction "1_1") (pintype "passive"))
      (node (ref "R39") (pin "1") (pinfunction "1_1") (pintype "passive"))
      (node (ref "R44") (pin "3") (pinfunction "3_3") (pintype "passive"))
      (node (ref "R45") (pin "1") (pinfunction "1_1") (pintype "passive"))
      (node (ref "R48") (pin "1") (pinfunction "1_1") (pintype "passive"))
      (node (ref "R49") (pin "1") (pinfunction "1_1") (pintype "passive"))
      (node (ref "R50") (pin "1") (pinfunction "1_1") (pintype "passive"))
      (node (ref "R52") (pin "3") (pinfunction "3_3") (pintype "passive"))
      (node (ref "R53") (pin "1") (pinfunction "1_1") (pintype "passive"))
      (node (ref "R54") (pin "1") (pinfunction "1_1") (pintype "passive"))
      (node (ref "R65") (pin "1") (pinfunction "1_1") (pintype "passive"))
      (node (ref "R67") (pin "1") (pinfunction "1_1") (pintype "passive"))
      (node (ref "R75") (pin "1") (pinfunction "1_1") (pintype "passive"))
      (node (ref "R84") (pin "1") (pinfunction "1_1") (pintype "passive"))
      (node (ref "R85") (pin "1") (pinfunction "1_1") (pintype "passive"))
      (node (ref "R87") (pin "1") (pinfunction "1_1") (pintype "passive"))
      (node (ref "R88") (pin "1") (pinfunction "1_1") (pintype "passive"))
      (node (ref "U6") (pin "11") (pinfunction "VSS_11") (pintype "passive"))
      (node (ref "U6") (pin "24") (pinfunction "VSSA_24") (pintype "passive"))
      (node (ref "U7") (pin "3") (pinfunction "ET_3") (pintype "passive"))
    )
    (net (code "37") (name "MCU_3.3V") (class "Default")
      (node (ref "J11") (pin "2") (pinfunction "2_2") (pintype "passive"))
    )
    (net (code "38") (name "Net-(C19-Pad1)") (class "Default")
      (node (ref "C19") (pin "1") (pinfunction "1_1") (pintype "passive"))
      (node (ref "R23") (pin "1") (pinfunction "1_1") (pintype "passive"))
    )
    (net (code "39") (name "Net-(C20-Pad1)") (class "Default")
      (node (ref "C20") (pin "1") (pinfunction "1_1") (pintype "passive"))
      (node (ref "R22") (pin "1") (pinfunction "1_1") (pintype "passive"))
    )
    (net (code "40") (name "Net-(C21-Pad1)") (class "Default")
      (node (ref "C21") (pin "1") (pinfunction "1_1") (pintype "passive"))
      (node (ref "R24") (pin "2") (pinfunction "2_2") (pintype "passive"))
      (node (ref "R29") (pin "2") (pinfunction "2_2") (pintype "passive"))
      (node (ref "R30") (pin "2") (pinfunction "2_2") (pintype "passive"))
    )
    (net (code "41") (name "Net-(C22-Pad2)") (class "Default")
      (node (ref "C22") (pin "2") (pinfunction "2_2") (pintype "passive"))
      (node (ref "R27") (pin "2") (pinfunction "2_2") (pintype "passive"))
    )
    (net (code "42") (name "Net-(C25-Pad2)") (class "Default")
      (node (ref "C25") (pin "2") (pinfunction "2_2") (pintype "passive"))
      (node (ref "J4") (pin "1") (pinfunction "1_1") (pintype "passive"))
    )
    (net (code "43") (name "Net-(C26-Pad2)") (class "Default")
      (node (ref "C26") (pin "2") (pinfunction "2_2") (pintype "passive"))
      (node (ref "C27") (pin "2") (pinfunction "2_2") (pintype "passive"))
      (node (ref "J4") (pin "3") (pinfunction "3_3") (pintype "passive"))
    )
    (net (code "44") (name "Net-(C30-Pad2)") (class "Default")
      (node (ref "C30") (pin "2") (pinfunction "2_2") (pintype "passive"))
      (node (ref "J6") (pin "2") (pinfunction "2_2") (pintype "passive"))
      (node (ref "R36") (pin "1") (pinfunction "1_1") (pintype "passive"))
      (node (ref "TP11") (pin "1") (pinfunction "1_1") (pintype "passive"))
    )
    (net (code "45") (name "Net-(C34-Pad2)") (class "Default")
      (node (ref "C34") (pin "2") (pinfunction "2_2") (pintype "passive"))
      (node (ref "J7") (pin "2") (pinfunction "2_2") (pintype "passive"))
    )
    (net (code "46") (name "Net-(C35-Pad2)") (class "Default")
      (node (ref "C35") (pin "2") (pinfunction "2_2") (pintype "passive"))
      (node (ref "R43") (pin "1") (pinfunction "1_1") (pintype "passive"))
      (node (ref "R48") (pin "2") (pinfunction "2_2") (pintype "passive"))
    )
    (net (code "47") (name "Net-(C36-Pad2)") (class "Default")
      (node (ref "C36") (pin "2") (pinfunction "2_2") (pintype "passive"))
      (node (ref "R40") (pin "1") (pinfunction "1_1") (pintype "passive"))
      (node (ref "R49") (pin "2") (pinfunction "2_2") (pintype "passive"))
    )
    (net (code "48") (name "Net-(C37-Pad1)") (class "Default")
      (node (ref "C37") (pin "1") (pinfunction "1_1") (pintype "passive"))
      (node (ref "R51") (pin "1") (pinfunction "1_1") (pintype "passive"))
      (node (ref "R69") (pin "2") (pinfunction "2_2") (pintype "passive"))
    )
    (net (code "49") (name "Net-(C38-Pad2)") (class "Default")
      (node (ref "C38") (pin "2") (pinfunction "2_2") (pintype "passive"))
      (node (ref "J10") (pin "2") (pinfunction "2_2") (pintype "passive"))
    )
    (net (code "50") (name "Net-(C39-Pad2)") (class "Default")
      (node (ref "C39") (pin "2") (pinfunction "2_2") (pintype "passive"))
      (node (ref "J10") (pin "1") (pinfunction "1_1") (pintype "passive"))
      (node (ref "R52") (pin "2") (pinfunction "2_2") (pintype "passive"))
    )
    (net (code "51") (name "Net-(C41-Pad1)") (class "Default")
      (node (ref "C41") (pin "1") (pinfunction "1_1") (pintype "passive"))
      (node (ref "C43") (pin "1") (pinfunction "1_1") (pintype "passive"))
      (node (ref "R55") (pin "2") (pinfunction "2_2") (pintype "passive"))
    )
    (net (code "52") (name "Net-(C41-Pad2)") (class "Default")
      (node (ref "C41") (pin "2") (pinfunction "2_2") (pintype "passive"))
      (node (ref "J9") (pin "2") (pinfunction "2_2") (pintype "passive"))
    )
    (net (code "53") (name "Net-(C42-Pad2)") (class "Default")
      (node (ref "C42") (pin "2") (pinfunction "2_2") (pintype "passive"))
      (node (ref "R56") (pin "1") (pinfunction "1_1") (pintype "passive"))
    )
    (net (code "54") (name "Net-(C52-Pad2)") (class "Default")
      (node (ref "C52") (pin "2") (pinfunction "2_2") (pintype "passive"))
      (node (ref "R66") (pin "1") (pinfunction "1_1") (pintype "passive"))
      (node (ref "R67") (pin "2") (pinfunction "2_2") (pintype "passive"))
      (node (ref "R68") (pin "2") (pinfunction "2_2") (pintype "passive"))
    )
    (net (code "55") (name "Net-(C58-Pad1)") (class "Default")
      (node (ref "C58") (pin "1") (pinfunction "1_1") (pintype "passive"))
      (node (ref "R78") (pin "1") (pinfunction "1_1") (pintype "passive"))
    )
    (net (code "56") (name "Net-(C66-Pad1)") (class "Default")
      (node (ref "C66") (pin "1") (pinfunction "1_1") (pintype "passive"))
      (node (ref "J11") (pin "3") (pinfunction "3_3") (pintype "passive"))
      (node (ref "J13") (pin "3") (pinfunction "3_3") (pintype "passive"))
    )
    (net (code "57") (name "Net-(C66-Pad2)") (class "Default")
      (node (ref "C66") (pin "2") (pinfunction "2_2") (pintype "passive"))
      (node (ref "C67") (pin "1") (pinfunction "1_1") (pintype "passive"))
      (node (ref "R87") (pin "2") (pinfunction "2_2") (pintype "passive"))
    )
    (net (code "58") (name "Net-(C67-Pad2)") (class "Default")
      (node (ref "C67") (pin "2") (pinfunction "2_2") (pintype "passive"))
      (node (ref "J11") (pin "4") (pinfunction "4_4") (pintype "passive"))
      (node (ref "J12") (pin "3") (pinfunction "3_3") (pintype "passive"))
    )
    (net (code "59") (name "Net-(C69-Pad2)") (class "Default")
      (node (ref "C69") (pin "2") (pinfunction "2_2") (pintype "passive"))
      (node (ref "J13") (pin "1") (pinfunction "1_1") (pintype "passive"))
    )
    (net (code "60") (name "Net-(D2-AC1)") (class "Default")
      (node (ref "D2") (pin "2") (pinfunction "AC1_2") (pintype "passive"))
      (node (ref "D7") (pin "2") (pinfunction "A_2") (pintype "passive"))
      (node (ref "R26") (pin "2") (pinfunction "2_2") (pintype "passive"))
      (node (ref "R57") (pin "2") (pinfunction "2_2") (pintype "passive"))
      (node (ref "U7") (pin "2") (pinfunction "C_2") (pintype "passive"))
    )
    (net (code "61") (name "Net-(D2-AC2)") (class "Default")
      (node (ref "C37") (pin "2") (pinfunction "2_2") (pintype "passive"))
      (node (ref "D2") (pin "4") (pinfunction "AC2_4") (pintype "passive"))
      (node (ref "R32") (pin "2") (pinfunction "2_2") (pintype "passive"))
    )
    (net (code "62") (name "Net-(D5-K)") (class "Default")
      (node (ref "D5") (pin "1") (pinfunction "K_1") (pintype "passive"))
      (node (ref "D6") (pin "1") (pinfunction "K_1") (pintype "passive"))
      (node (ref "R41") (pin "1") (pinfunction "1_1") (pintype "passive"))
    )
    (net (code "63") (name "Net-(D7-K)") (class "Default")
      (node (ref "D7") (pin "1") (pinfunction "K_1") (pintype "passive"))
      (node (ref "R51") (pin "2") (pinfunction "2_2") (pintype "passive"))
      (node (ref "TP13") (pin "1") (pinfunction "1_1") (pintype "passive"))
      (node (ref "U7") (pin "1") (pinfunction "A_1") (pintype "passive"))
    )
    (net (code "64") (name "Net-(D8-A)") (class "Default")
      (node (ref "D8") (pin "2") (pinfunction "A_2") (pintype "passive"))
      (node (ref "R58") (pin "1") (pinfunction "1_1") (pintype "passive"))
    )
    (net (code "65") (name "Net-(D11-AC1)") (class "Default")
      (node (ref "D11") (pin "2") (pinfunction "AC1_2") (pintype "passive"))
      (node (ref "R57") (pin "1") (pinfunction "1_1") (pintype "passive"))
    )
    (net (code "66") (name "Net-(D11-AC2)") (class "Default")
      (node (ref "D11") (pin "4") (pinfunction "AC2_4") (pintype "passive"))
      (node (ref "R69") (pin "1") (pinfunction "1_1") (pintype "passive"))
    )
    (net (code "67") (name "Net-(D11-POS)") (class "Default")
      (node (ref "D11") (pin "1") (pinfunction "POS_1") (pintype "passive"))
      (node (ref "Q10") (pin "3") (pinfunction "C_3") (pintype "passive"))
      (node (ref "R63") (pin "2") (pinfunction "2_2") (pintype "passive"))
      (node (ref "R66") (pin "2") (pinfunction "2_2") (pintype "passive"))
      (node (ref "R70") (pin "1") (pinfunction "1_1") (pintype "passive"))
      (node (ref "TP20") (pin "1") (pinfunction "1_1") (pintype "passive"))
    )
    (net (code "68") (name "Net-(J3-Pad1)") (class "Default")
      (node (ref "J3") (pin "1") (pinfunction "1_1") (pintype "passive"))
      (node (ref "R22") (pin "2") (pinfunction "2_2") (pintype "passive"))
    )
    (net (code "69") (name "Net-(J3-Pad3)") (class "Default")
      (node (ref "J3") (pin "3") (pinfunction "3_3") (pintype "passive"))
      (node (ref "R23") (pin "2") (pinfunction "2_2") (pintype "passive"))
    )
    (net (code "70") (name "Net-(J5-Pad3)") (class "Default")
      (node (ref "J5") (pin "3") (pinfunction "3_3") (pintype "passive"))
      (node (ref "R33") (pin "1") (pinfunction "1_1") (pintype "passive"))
    )
    (net (code "71") (name "Net-(J6-Pad3)") (class "Default")
      (node (ref "J6") (pin "3") (pinfunction "3_3") (pintype "passive"))
      (node (ref "R40") (pin "2") (pinfunction "2_2") (pintype "passive"))
      (node (ref "R50") (pin "2") (pinfunction "2_2") (pintype "passive"))
    )
    (net (code "72") (name "Net-(J7-Pad3)") (class "Default")
      (node (ref "J7") (pin "3") (pinfunction "3_3") (pintype "passive"))
      (node (ref "R44") (pin "2") (pinfunction "2_2") (pintype "passive"))
    )
    (net (code "73") (name "Net-(J8-Pad3)") (class "Default")
      (node (ref "J8") (pin "3") (pinfunction "3_3") (pintype "passive"))
      (node (ref "R55") (pin "1") (pinfunction "1_1") (pintype "passive"))
    )
    (net (code "74") (name "Net-(Q4-B)") (class "Default")
      (node (ref "Q4") (pin "2") (pinfunction "B_2") (pintype "passive"))
      (node (ref "Q5") (pin "1") (pinfunction "E_1") (pintype "passive"))
    )
    (net (code "75") (name "Net-(Q5-B)") (class "Default")
      (node (ref "Q5") (pin "2") (pinfunction "B_2") (pintype "passive"))
      (node (ref "R34") (pin "2") (pinfunction "2_2") (pintype "passive"))
      (node (ref "R37") (pin "2") (pinfunction "2_2") (pintype "passive"))
      (node (ref "TP10") (pin "1") (pinfunction "1_1") (pintype "passive"))
    )
    (net (code "76") (name "Net-(Q6-B)") (class "Default")
      (node (ref "Q6") (pin "1") (pinfunction "B_1") (pintype "passive"))
      (node (ref "U6") (pin "10") (pinfunction "CS_10") (pintype "passive"))
    )
    (net (code "77") (name "Net-(Q6-E)") (class "Default")
      (node (ref "Q6") (pin "2") (pinfunction "E_2") (pintype "passive"))
      (node (ref "Q9") (pin "2") (pinfunction "E_2") (pintype "passive"))
      (node (ref "R24") (pin "1") (pinfunction "1_1") (pintype "passive"))
      (node (ref "R31") (pin "1") (pinfunction "1_1") (pintype "passive"))
      (node (ref "R36") (pin "2") (pinfunction "2_2") (pintype "passive"))
      (node (ref "U6") (pin "12") (pinfunction "LI_12") (pintype "passive"))
    )
    (net (code "78") (name "Net-(Q7-B)") (class "Default")
      (node (ref "Q7") (pin "2") (pinfunction "B_2") (pintype "passive"))
      (node (ref "R42") (pin "2") (pinfunction "2_2") (pintype "passive"))
      (node (ref "R45") (pin "2") (pinfunction "2_2") (pintype "passive"))
    )
    (net (code "79") (name "Net-(Q7-C)") (class "Default")
      (node (ref "Q7") (pin "3") (pinfunction "C_3") (pintype "passive"))
      (node (ref "Q8") (pin "3") (pinfunction "C_3") (pintype "passive"))
      (node (ref "R37") (pin "1") (pinfunction "1_1") (pintype "passive"))
    )
    (net (code "80") (name "Net-(Q8-B)") (class "Default")
      (node (ref "Q8") (pin "2") (pinfunction "B_2") (pintype "passive"))
      (node (ref "R46") (pin "2") (pinfunction "2_2") (pintype "passive"))
    )
    (net (code "81") (name "Net-(Q9-B)") (class "Default")
      (node (ref "Q9") (pin "1") (pinfunction "B_1") (pintype "passive"))
      (node (ref "U6") (pin "14") (pinfunction "SS_14") (pintype "passive"))
    )
    (net (code "82") (name "Net-(Q10-B)") (class "Default")
      (node (ref "C47") (pin "1") (pinfunction "1_1") (pintype "passive"))
      (node (ref "D9") (pin "1") (pinfunction "1_1") (pintype "passive"))
      (node (ref "Q10") (pin "2") (pinfunction "B_2") (pintype "passive"))
      (node (ref "R63") (pin "1") (pinfunction "1_1") (pintype "passive"))
    )
    (net (code "83") (name "Net-(Q11-B)") (class "Default")
      (node (ref "Q11") (pin "1") (pinfunction "B_1") (pintype "passive"))
      (node (ref "Q12") (pin "3") (pinfunction "C_3") (pintype "passive"))
      (node (ref "R86") (pin "2") (pinfunction "2_2") (pintype "passive"))
    )
    (net (code "84") (name "Net-(Q11-C)") (class "Default")
      (node (ref "C57") (pin "2") (pinfunction "2_2") (pintype "passive"))
      (node (ref "Q11") (pin "3") (pinfunction "C_3") (pintype "passive"))
      (node (ref "R76") (pin "1") (pinfunction "1_1") (pintype "passive"))
      (node (ref "R77") (pin "1") (pinfunction "1_1") (pintype "passive"))
      (node (ref "R79") (pin "1") (pinfunction "1_1") (pintype "passive"))
    )
    (net (code "85") (name "Net-(Q11-E)") (class "Default")
      (node (ref "Q11") (pin "2") (pinfunction "E_2") (pintype "passive"))
      (node (ref "Q12") (pin "1") (pinfunction "B_1") (pintype "passive"))
      (node (ref "R76") (pin "2") (pinfunction "2_2") (pintype "passive"))
      (node (ref "R79") (pin "2") (pinfunction "2_2") (pintype "passive"))
      (node (ref "R80") (pin "2") (pinfunction "2_2") (pintype "passive"))
    )
    (net (code "86") (name "Net-(R25-Pad2)") (class "Default")
      (node (ref "R25") (pin "2") (pinfunction "2_2") (pintype "passive"))
      (node (ref "R27") (pin "1") (pinfunction "1_1") (pintype "passive"))
    )
    (net (code "87") (name "Net-(R41-Pad2)") (class "Default")
      (node (ref "R41") (pin "2") (pinfunction "2_2") (pintype "passive"))
      (node (ref "R42") (pin "1") (pinfunction "1_1") (pintype "passive"))
      (node (ref "TP12") (pin "1") (pinfunction "1_1") (pintype "passive"))
    )
    (net (code "88") (name "Net-(R64-Pad1)") (class "Default")
      (node (ref "R64") (pin "1") (pinfunction "1_1") (pintype "passive"))
      (node (ref "R65") (pin "2") (pinfunction "2_2") (pintype "passive"))
    )
    (net (code "89") (name "Net-(R82-Pad1)") (class "Default")
      (node (ref "R82") (pin "1") (pinfunction "1_1") (pintype "passive"))
      (node (ref "R83") (pin "2") (pinfunction "2_2") (pintype "passive"))
      (node (ref "R85") (pin "2") (pinfunction "2_2") (pintype "passive"))
    )
    (net (code "90") (name "Net-(R86-Pad1)") (class "Default")
      (node (ref "R86") (pin "1") (pinfunction "1_1") (pintype "passive"))
      (node (ref "R88") (pin "2") (pinfunction "2_2") (pintype "passive"))
    )
    (net (code "91") (name "Net-(U6-CBN)") (class "Default")
      (node (ref "C51") (pin "1") (pinfunction "1_1") (pintype "passive"))
      (node (ref "R64") (pin "2") (pinfunction "2_2") (pintype "passive"))
      (node (ref "U6") (pin "1") (pinfunction "CBN_1") (pintype "passive"))
    )
    (net (code "92") (name "Net-(U6-CI)") (class "Default")
      (node (ref "C33") (pin "2") (pinfunction "2_2") (pintype "passive"))
      (node (ref "U6") (pin "16") (pinfunction "CI_16") (pintype "passive"))
    )
    (net (code "93") (name "Net-(U6-CLK{slash}HEI)") (class "Default")
      (node (ref "R61") (pin "1") (pinfunction "1_1") (pintype "passive"))
      (node (ref "U6") (pin "27") (pinfunction "CLK/HEI_27") (pintype "passive"))
    )
    (net (code "94") (name "Net-(U6-DI{slash}xPD)") (class "Default")
      (node (ref "R60") (pin "1") (pinfunction "1_1") (pintype "passive"))
      (node (ref "U6") (pin "26") (pinfunction "DI/xPD_26") (pintype "passive"))
    )
    (net (code "95") (name "Net-(U6-FT1)") (class "Default")
      (node (ref "C49") (pin "2") (pinfunction "2_2") (pintype "passive"))
      (node (ref "U6") (pin "2") (pinfunction "FT1_2") (pintype "passive"))
    )
    (net (code "96") (name "Net-(U6-LO)") (class "Default")
      (node (ref "C42") (pin "1") (pinfunction "1_1") (pintype "passive"))
      (node (ref "TP15") (pin "1") (pinfunction "1_1") (pintype "passive"))
      (node (ref "U6") (pin "23") (pinfunction "LO_23") (pintype "passive"))
    )
    (net (code "97") (name "Net-(U6-M3)") (class "Default")
      (node (ref "C24") (pin "1") (pinfunction "1_1") (pintype "passive"))
      (node (ref "J4") (pin "2") (pinfunction "2_2") (pintype "passive"))
      (node (ref "U6") (pin "7") (pinfunction "M3_7") (pintype "passive"))
    )
    (net (code "98") (name "Net-(U6-M4)") (class "Default")
      (node (ref "C25") (pin "1") (pinfunction "1_1") (pintype "passive"))
      (node (ref "C26") (pin "1") (pinfunction "1_1") (pintype "passive"))
      (node (ref "C27") (pin "1") (pinfunction "1_1") (pintype "passive"))
      (node (ref "C28") (pin "2") (pinfunction "2_2") (pintype "passive"))
      (node (ref "U6") (pin "5") (pinfunction "M4_5") (pintype "passive"))
    )
    (net (code "99") (name "Net-(U6-REC1)") (class "Default")
      (node (ref "C34") (pin "1") (pinfunction "1_1") (pintype "passive"))
      (node (ref "U6") (pin "20") (pinfunction "REC1_20") (pintype "passive"))
    )
    (net (code "100") (name "Net-(U6-RI)") (class "Default")
      (node (ref "C23") (pin "1") (pinfunction "1_1") (pintype "passive"))
      (node (ref "U6") (pin "13") (pinfunction "RI_13") (pintype "passive"))
    )
    (net (code "101") (name "Net-(U6-STB)") (class "Default")
      (node (ref "C30") (pin "1") (pinfunction "1_1") (pintype "passive"))
      (node (ref "U6") (pin "9") (pinfunction "STB_9") (pintype "passive"))
    )
    (net (code "102") (name "Net-(U6-TONE_IN)") (class "Default")
      (node (ref "C22") (pin "1") (pinfunction "1_1") (pintype "passive"))
      (node (ref "TP6") (pin "1") (pinfunction "1_1") (pintype "passive"))
      (node (ref "U6") (pin "28") (pinfunction "TONE_IN_28") (pintype "passive"))
    )
    (net (code "103") (name "Net-(U6-xCS{slash}xMUTE)") (class "Default")
      (node (ref "R59") (pin "1") (pinfunction "1_1") (pintype "passive"))
      (node (ref "U6") (pin "25") (pinfunction "xCS/xMUTE_25") (pintype "passive"))
    )
    (net (code "104") (name "Net-(U8-HFI)") (class "Default")
      (node (ref "C55") (pin "2") (pinfunction "2_2") (pintype "passive"))
      (node (ref "R71") (pin "1") (pinfunction "1_1") (pintype "passive"))
      (node (ref "U8") (pin "7") (pinfunction "HFI_7") (pintype "passive"))
    )
    (net (code "105") (name "Net-(U8-HFO)") (class "Default")
      (node (ref "R71") (pin "2") (pinfunction "2_2") (pintype "passive"))
      (node (ref "U8") (pin "6") (pinfunction "HFO_6") (pintype "passive"))
    )
    (net (code "106") (name "Net-(U8-LFI)") (class "Default")
      (node (ref "C56") (pin "1") (pinfunction "1_1") (pintype "passive"))
      (node (ref "R74") (pin "1") (pinfunction "1_1") (pintype "passive"))
      (node (ref "U8") (pin "3") (pinfunction "LFI_3") (pintype "passive"))
    )
    (net (code "107") (name "Net-(U8-LFO)") (class "Default")
      (node (ref "R74") (pin "2") (pinfunction "2_2") (pintype "passive"))
      (node (ref "U8") (pin "4") (pinfunction "LFO_4") (pintype "passive"))
    )
    (net (code "108") (name "Net-(U8-OUT)") (class "Default")
      (node (ref "C53") (pin "1") (pinfunction "1_1") (pintype "passive"))
      (node (ref "U8") (pin "8") (pinfunction "OUT_8") (pintype "passive"))
    )
    (net (code "109") (name "Net-(U8-RSL)") (class "Default")
      (node (ref "R73") (pin "2") (pinfunction "2_2") (pintype "passive"))
      (node (ref "U8") (pin "2") (pinfunction "RSL_2") (pintype "passive"))
    )
    (net (code "110") (name "Net-(U8-VCC)") (class "Default")
      (node (ref "C54") (pin "2") (pinfunction "2_2") (pintype "passive"))
      (node (ref "D12") (pin "1") (pinfunction "1_1") (pintype "passive"))
      (node (ref "R70") (pin "2") (pinfunction "2_2") (pintype "passive"))
      (node (ref "R72") (pin "2") (pinfunction "2_2") (pintype "passive"))
      (node (ref "U8") (pin "1") (pinfunction "VCC_1") (pintype "passive"))
    )
    (net (code "111") (name "VDD") (class "Default")
      (node (ref "C47") (pin "2") (pinfunction "2_2") (pintype "passive"))
      (node (ref "C50") (pin "1") (pinfunction "1_1") (pintype "passive"))
      (node (ref "C61") (pin "2") (pinfunction "2_2") (pintype "passive"))
      (node (ref "D10") (pin "1") (pinfunction "1_1") (pintype "passive"))
      (node (ref "D8") (pin "1") (pinfunction "K_1") (pintype "passive"))
      (node (ref "Q10") (pin "1") (pinfunction "E_1") (pintype "passive"))
      (node (ref "R62") (pin "2") (pinfunction "2_2") (pintype "passive"))
      (node (ref "TP19") (pin "1") (pinfunction "1_1") (pintype "passive"))
      (node (ref "U6") (pin "18") (pinfunction "VDD_18") (pintype "passive"))
    )
    (net (code "112") (name "VPP") (class "Default")
      (node (ref "C40") (pin "1") (pinfunction "1_1") (pintype "passive"))
      (node (ref "Q9") (pin "3") (pinfunction "C_3") (pintype "passive"))
      (node (ref "R58") (pin "2") (pinfunction "2_2") (pintype "passive"))
      (node (ref "U6") (pin "22") (pinfunction "VPP_22") (pintype "passive"))
    )
  )
)
